# jr-support_v4.net
KiCad netlist of a schematic drawn in EAGLE
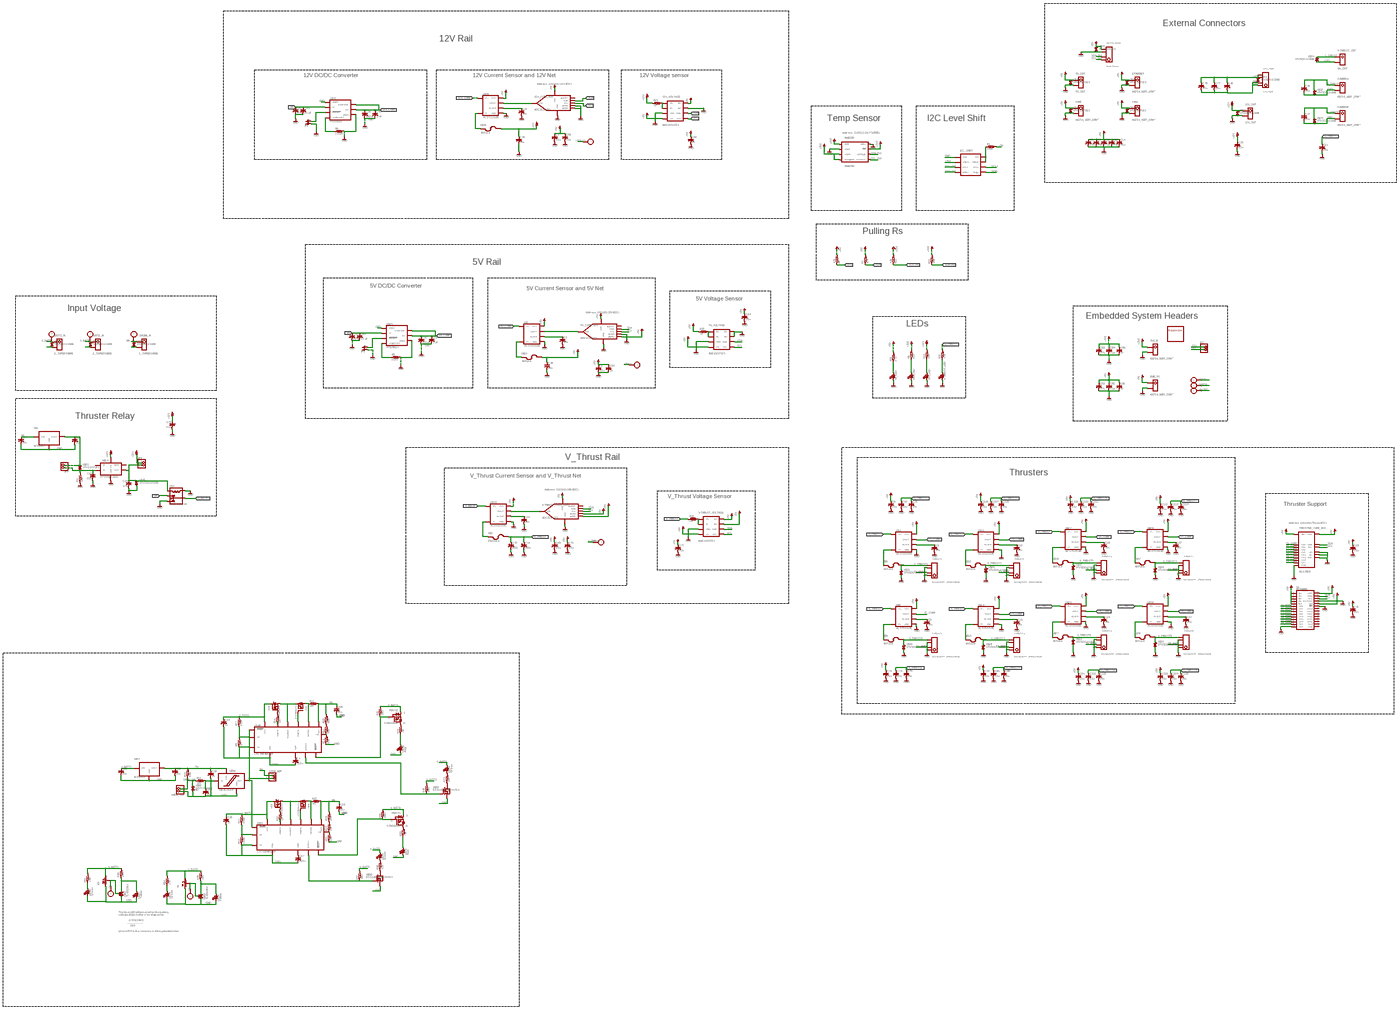
[diagram p0: schematic, sheet 1, overview]
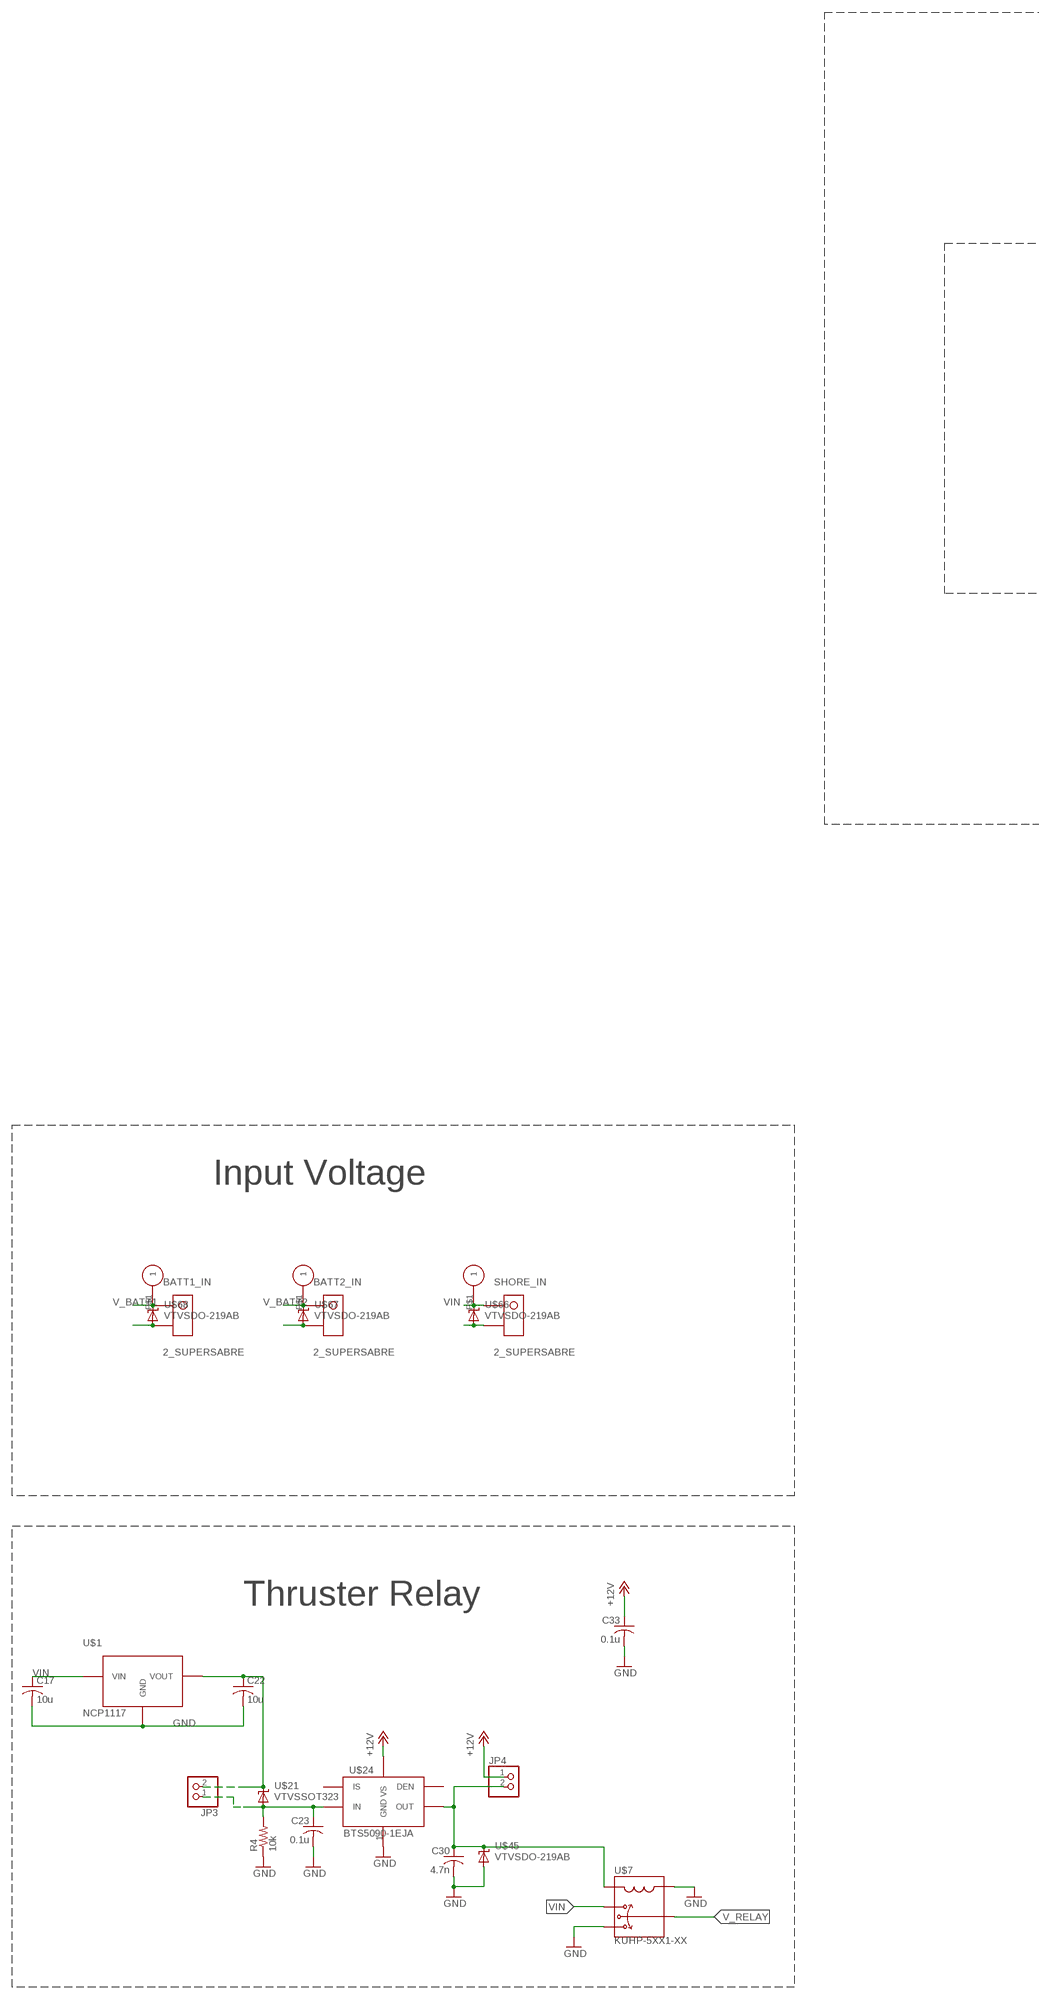
[diagram p1: schematic, sheet 1, part 1 of 8]
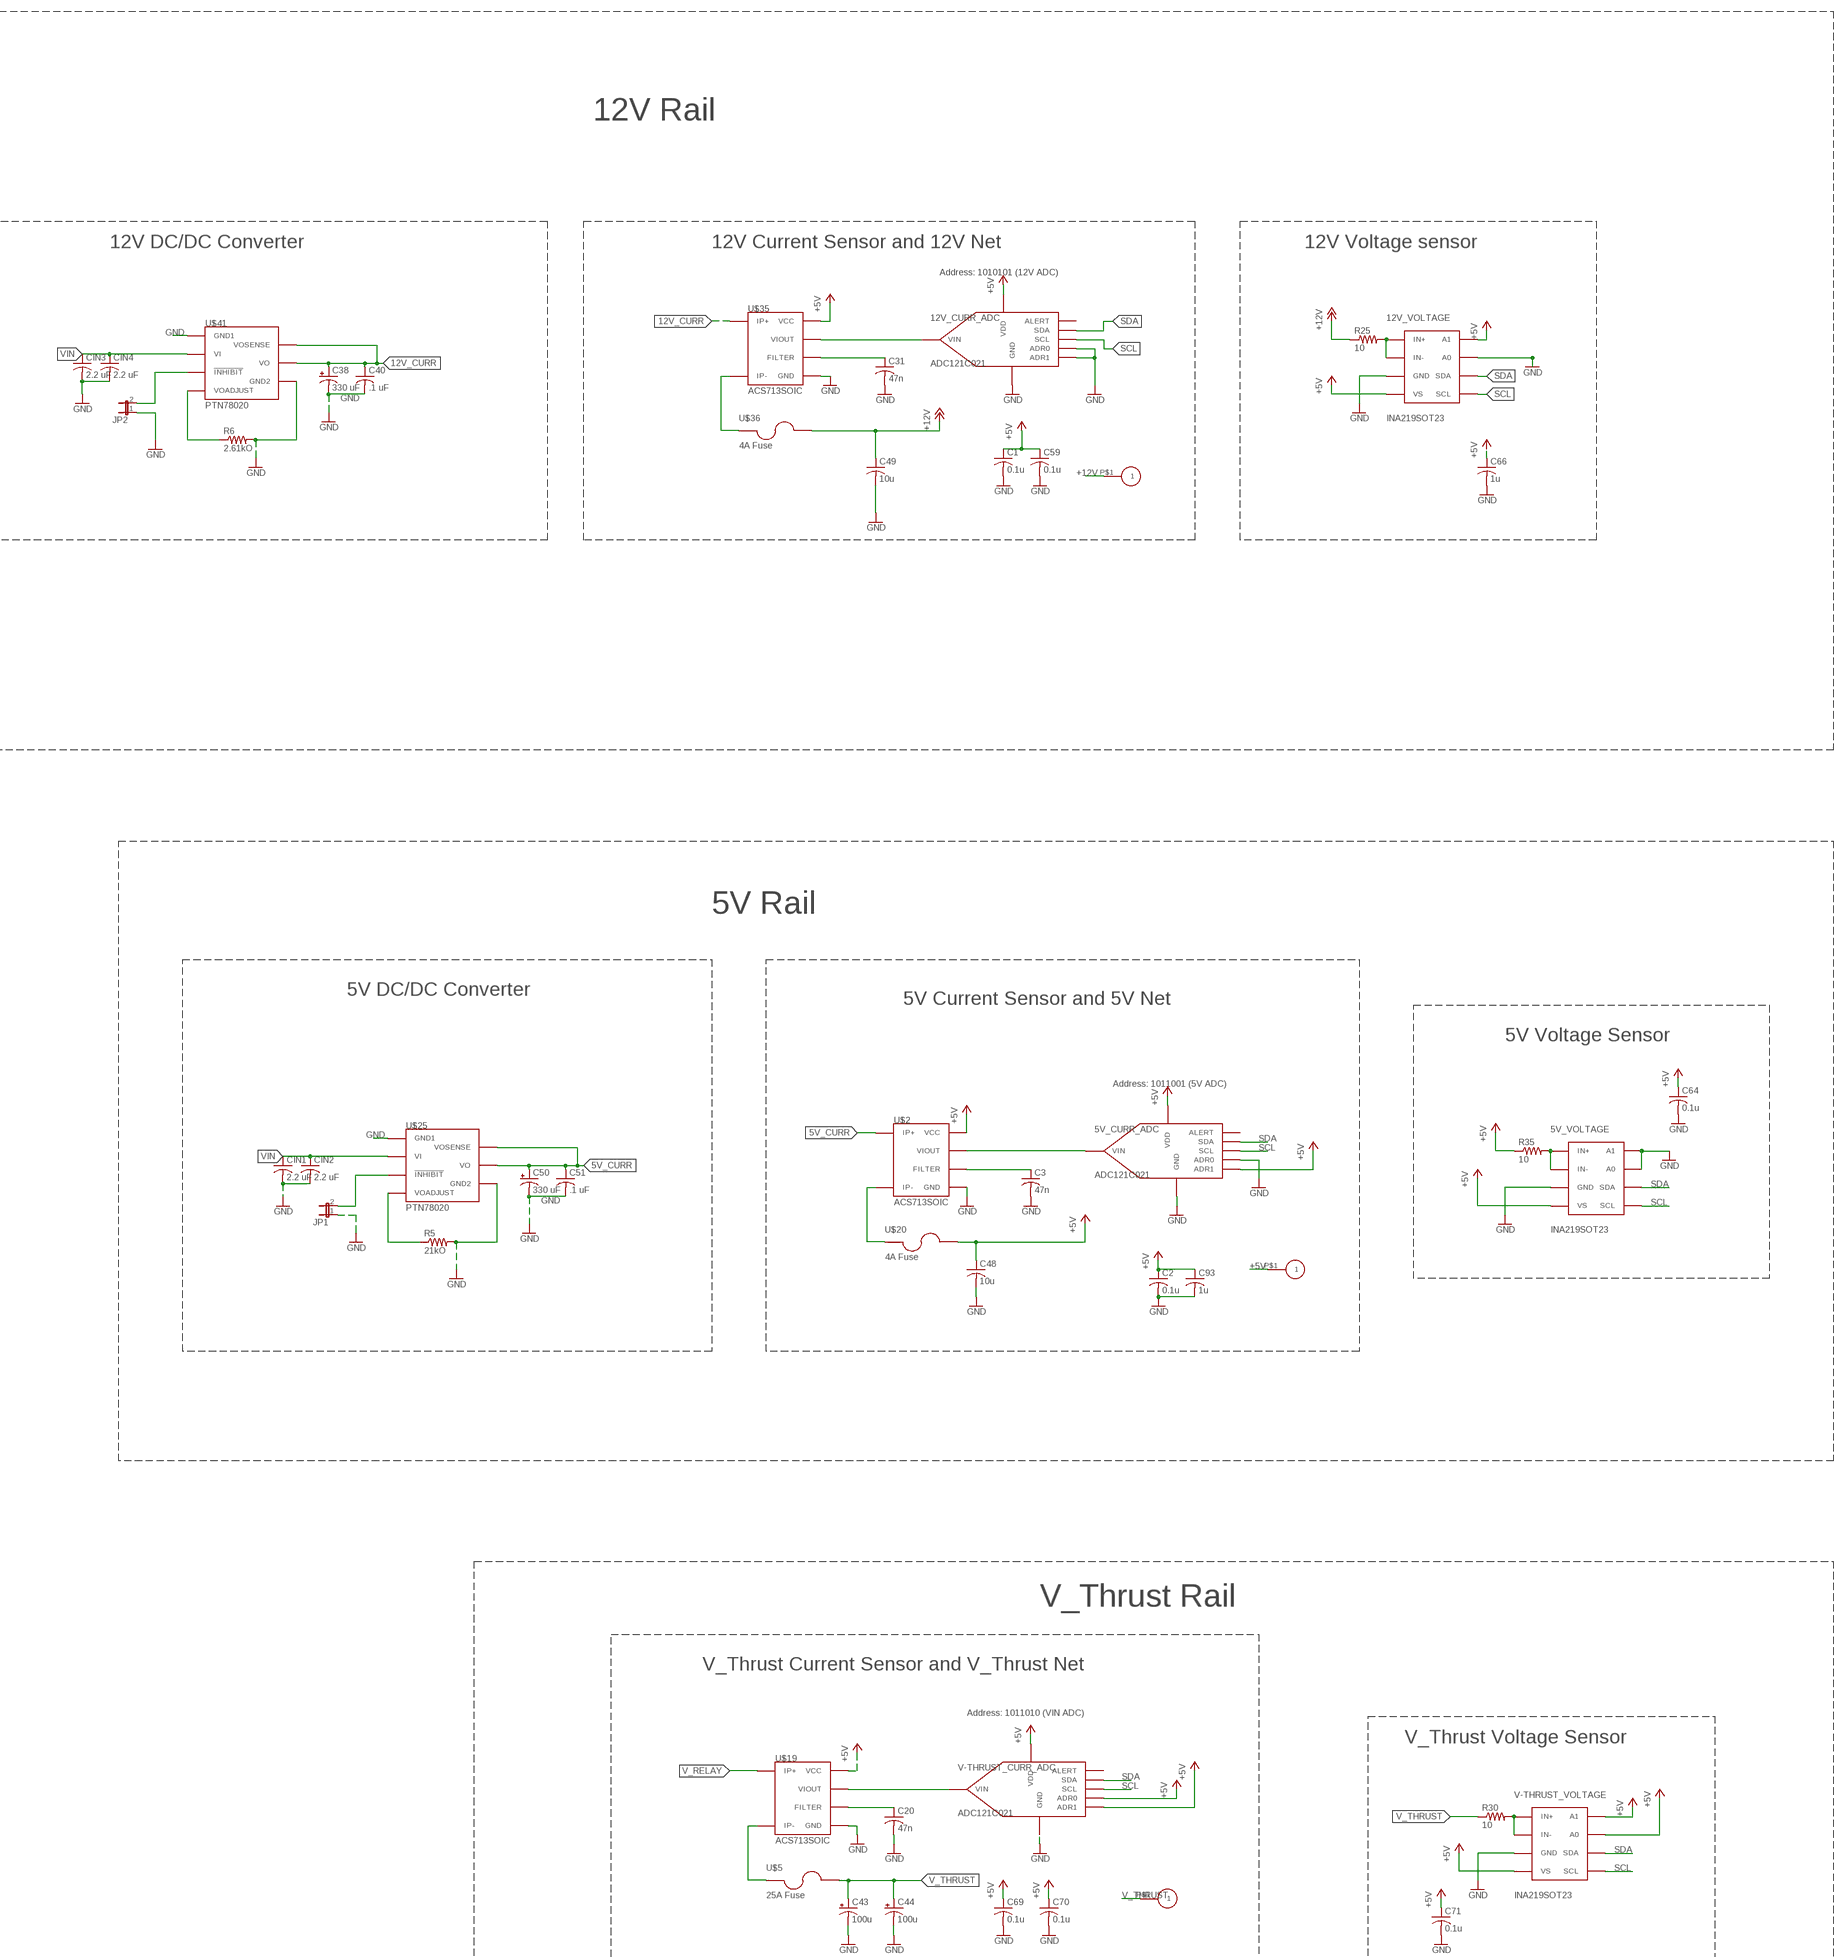
[diagram p2: schematic, sheet 1, part 2 of 8]
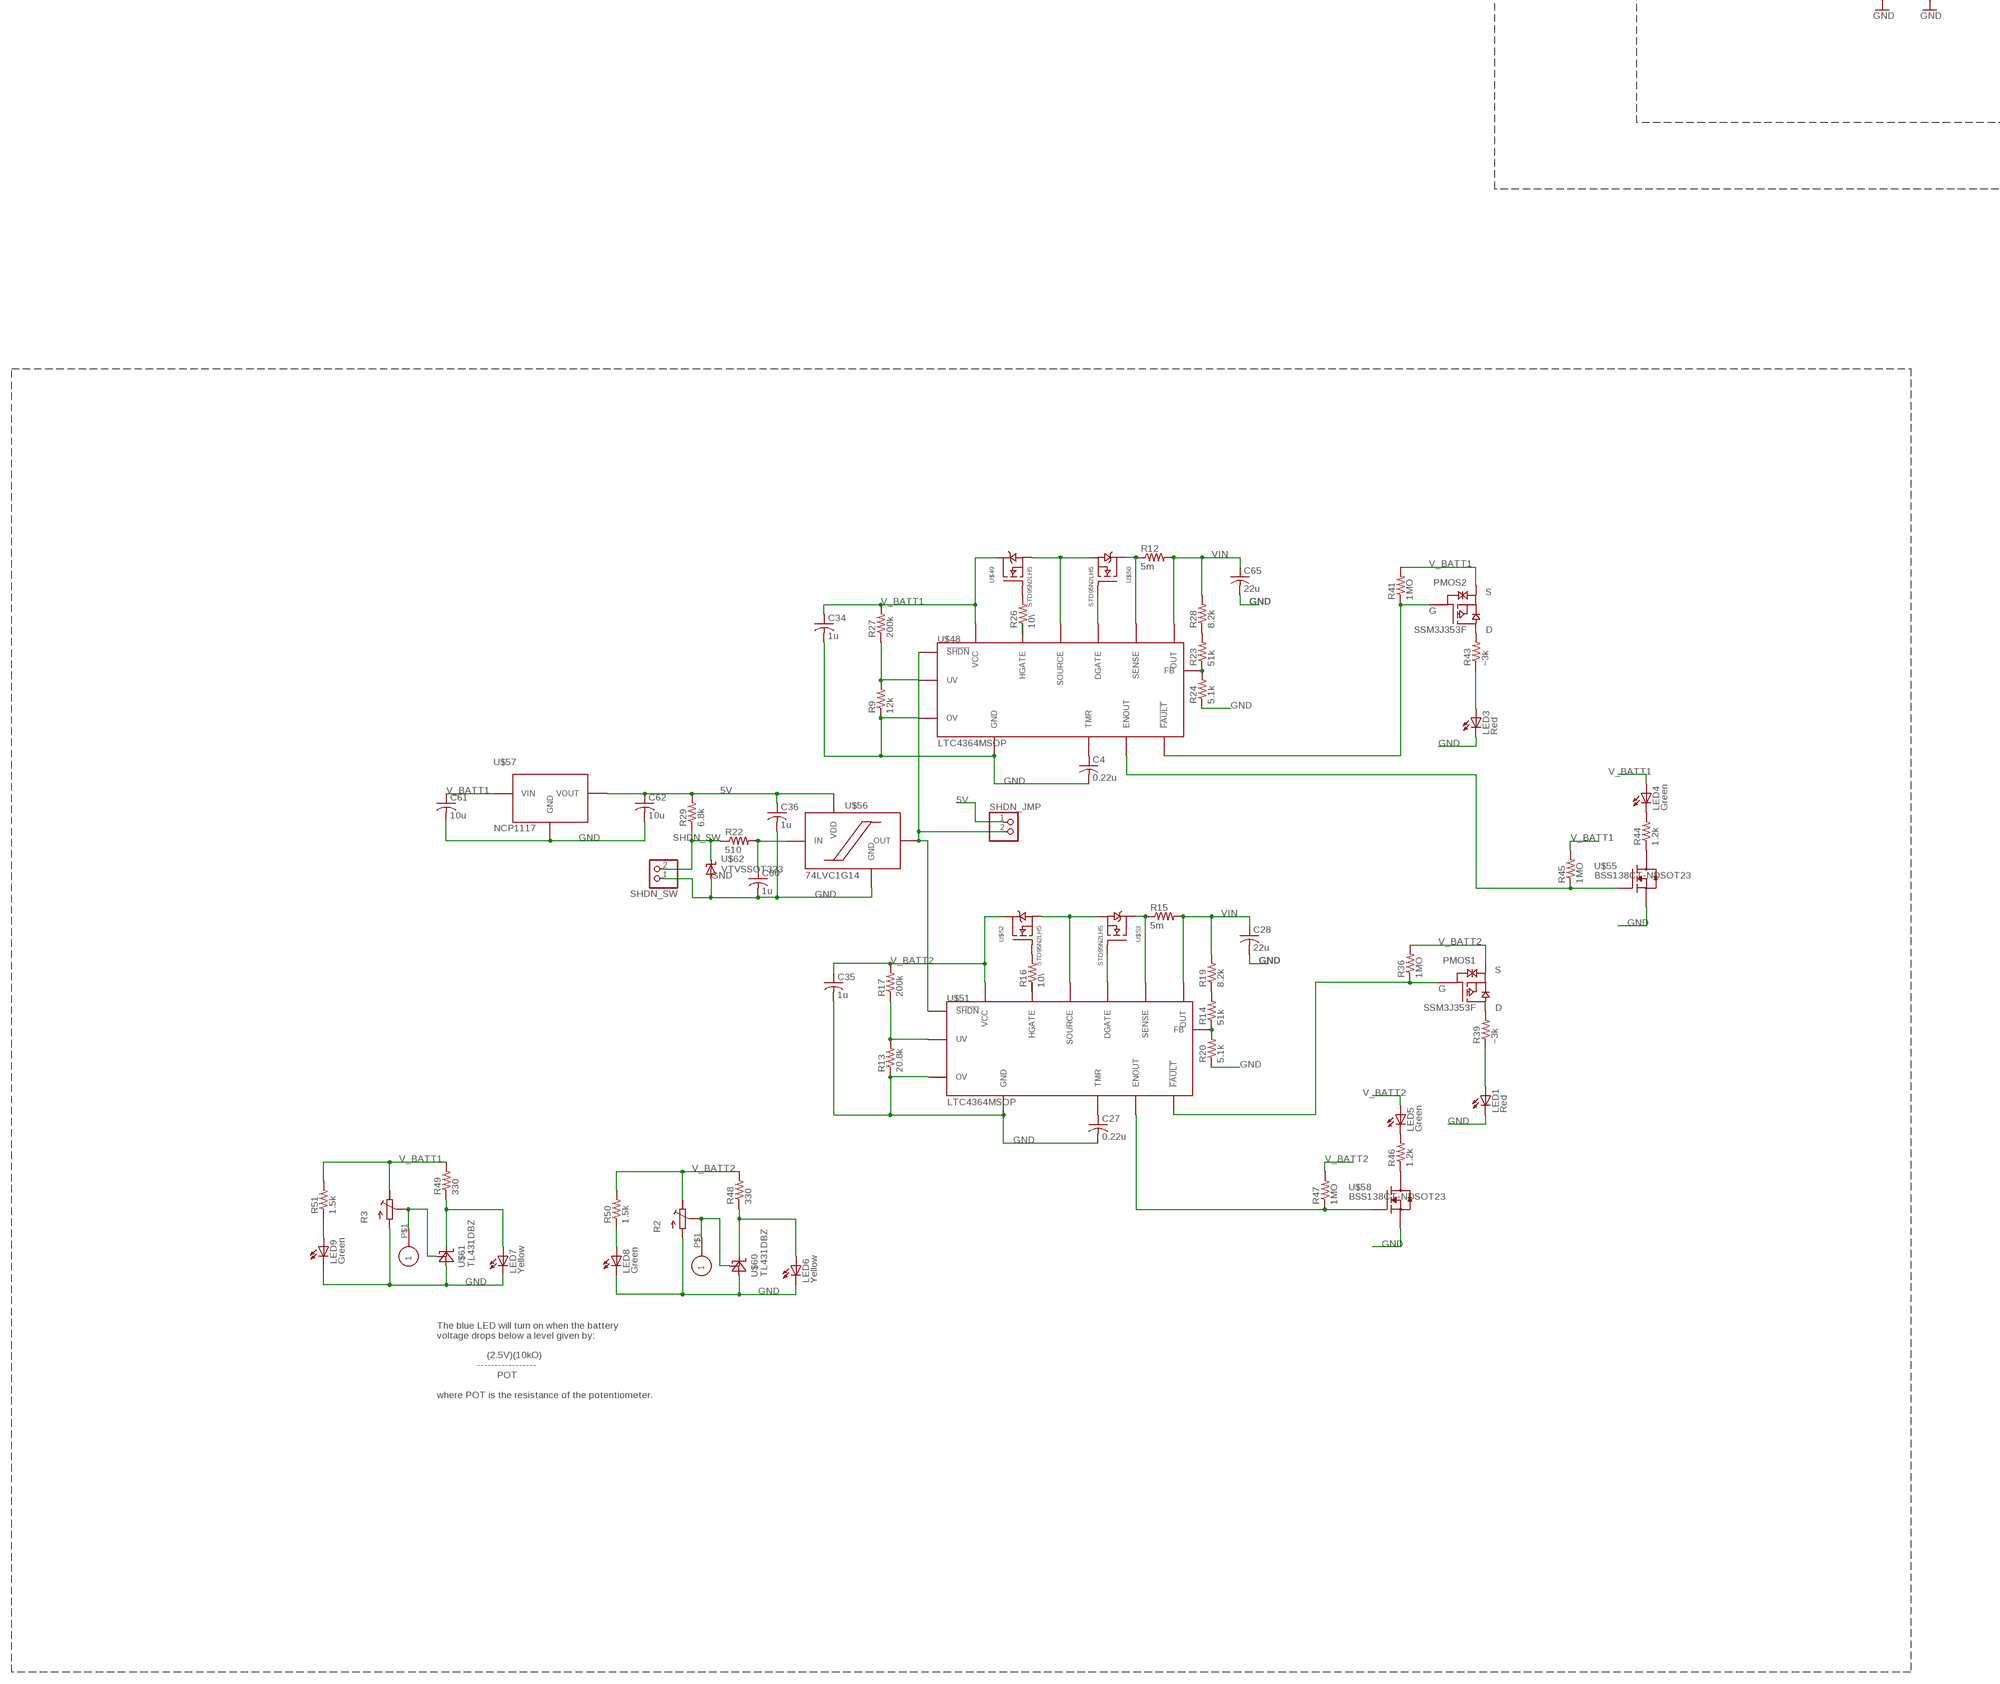
[diagram p3: schematic, sheet 1, part 3 of 8]
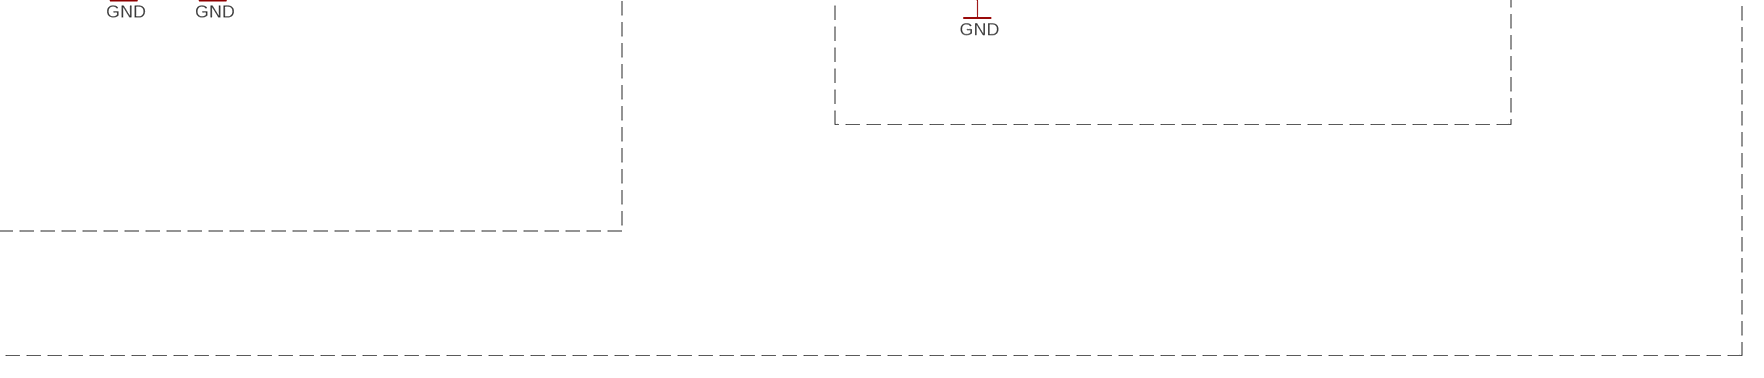
[diagram p4: schematic, sheet 1, part 4 of 8]
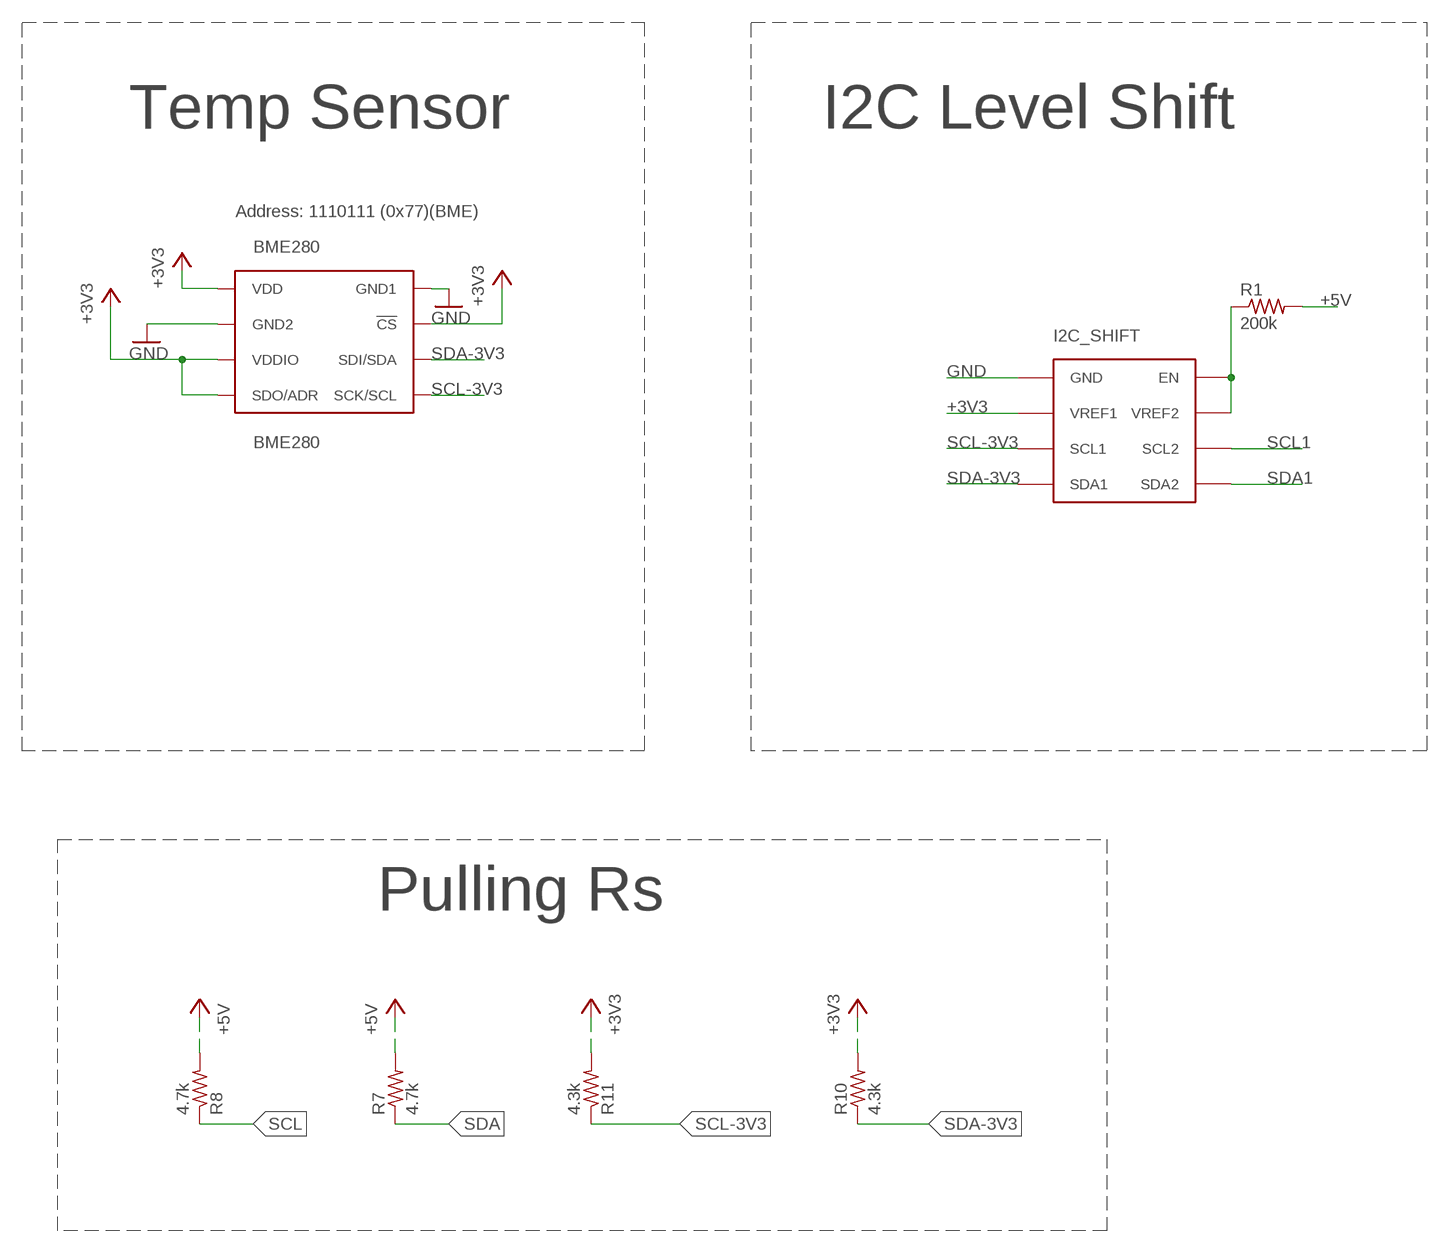
[diagram p5: schematic, sheet 1, part 5 of 8]
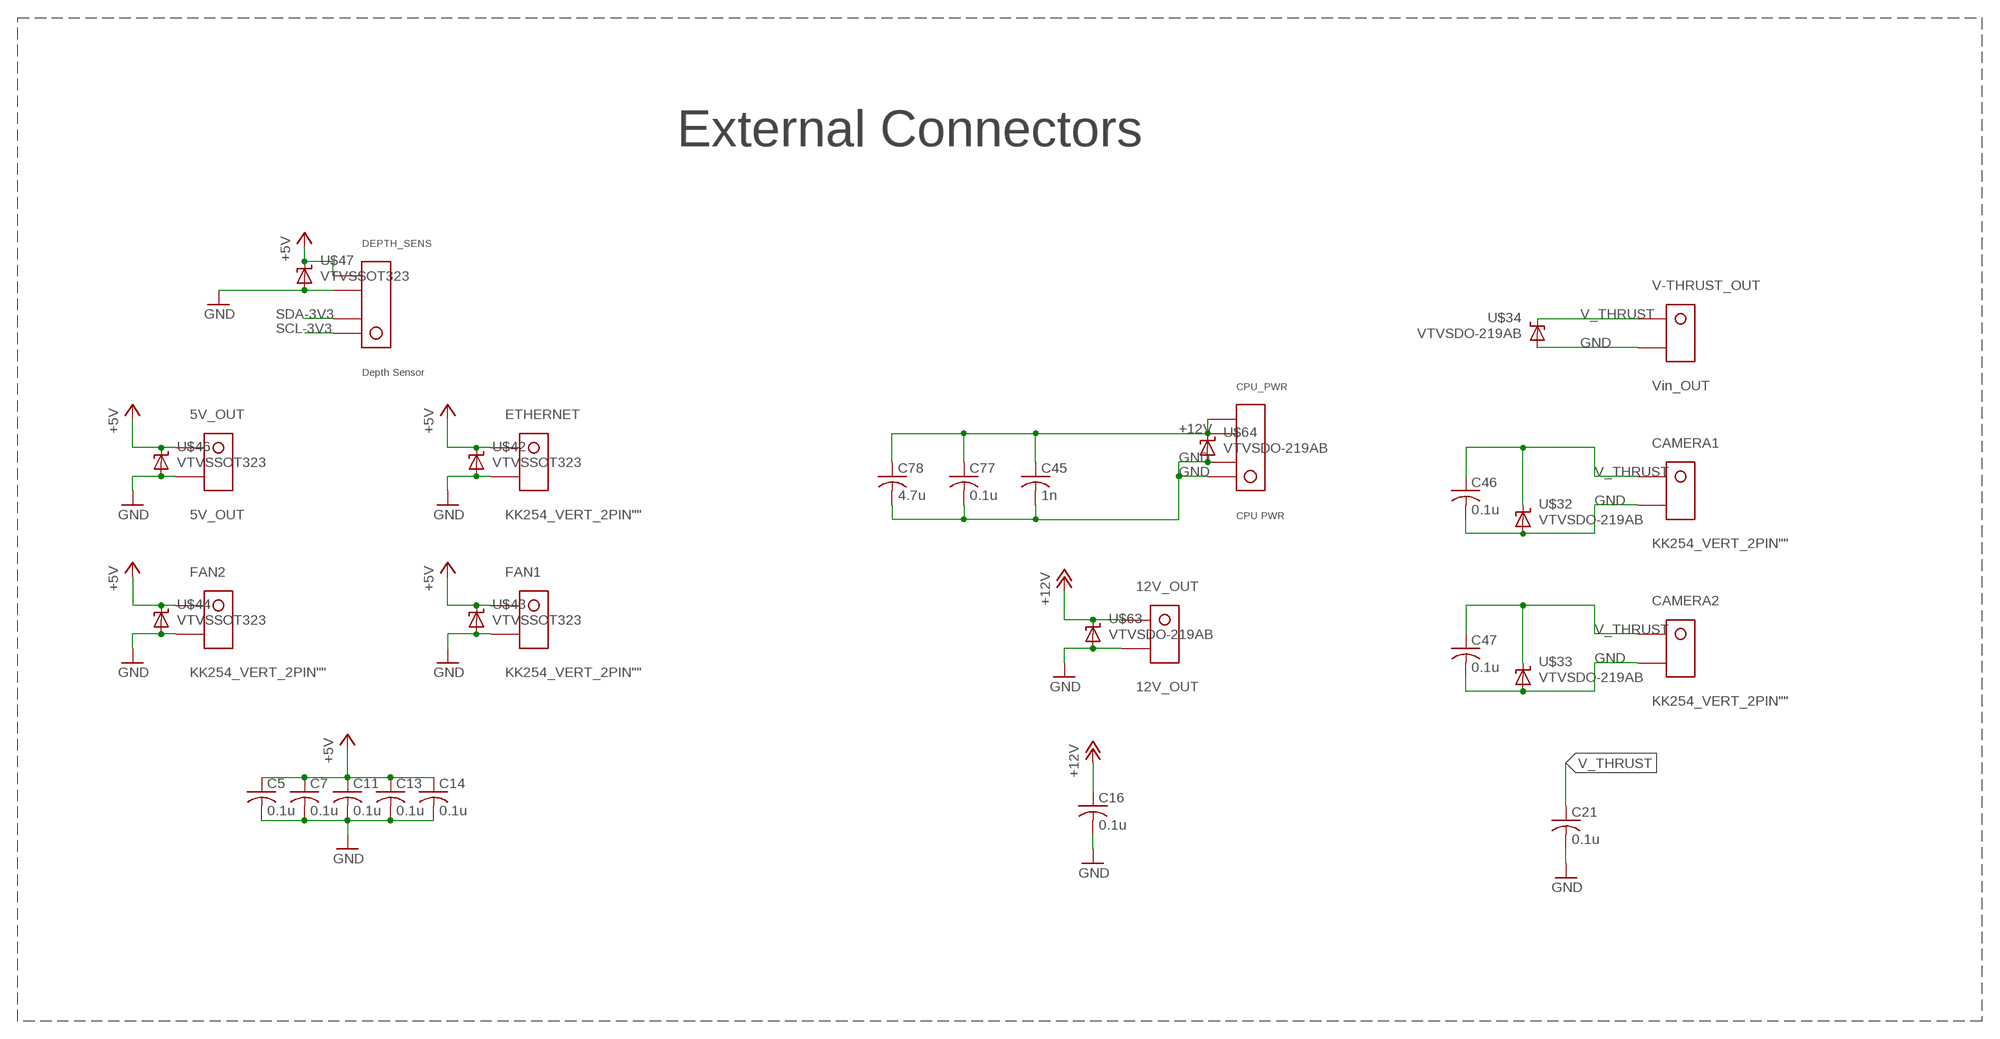
[diagram p6: schematic, sheet 1, part 6 of 8]
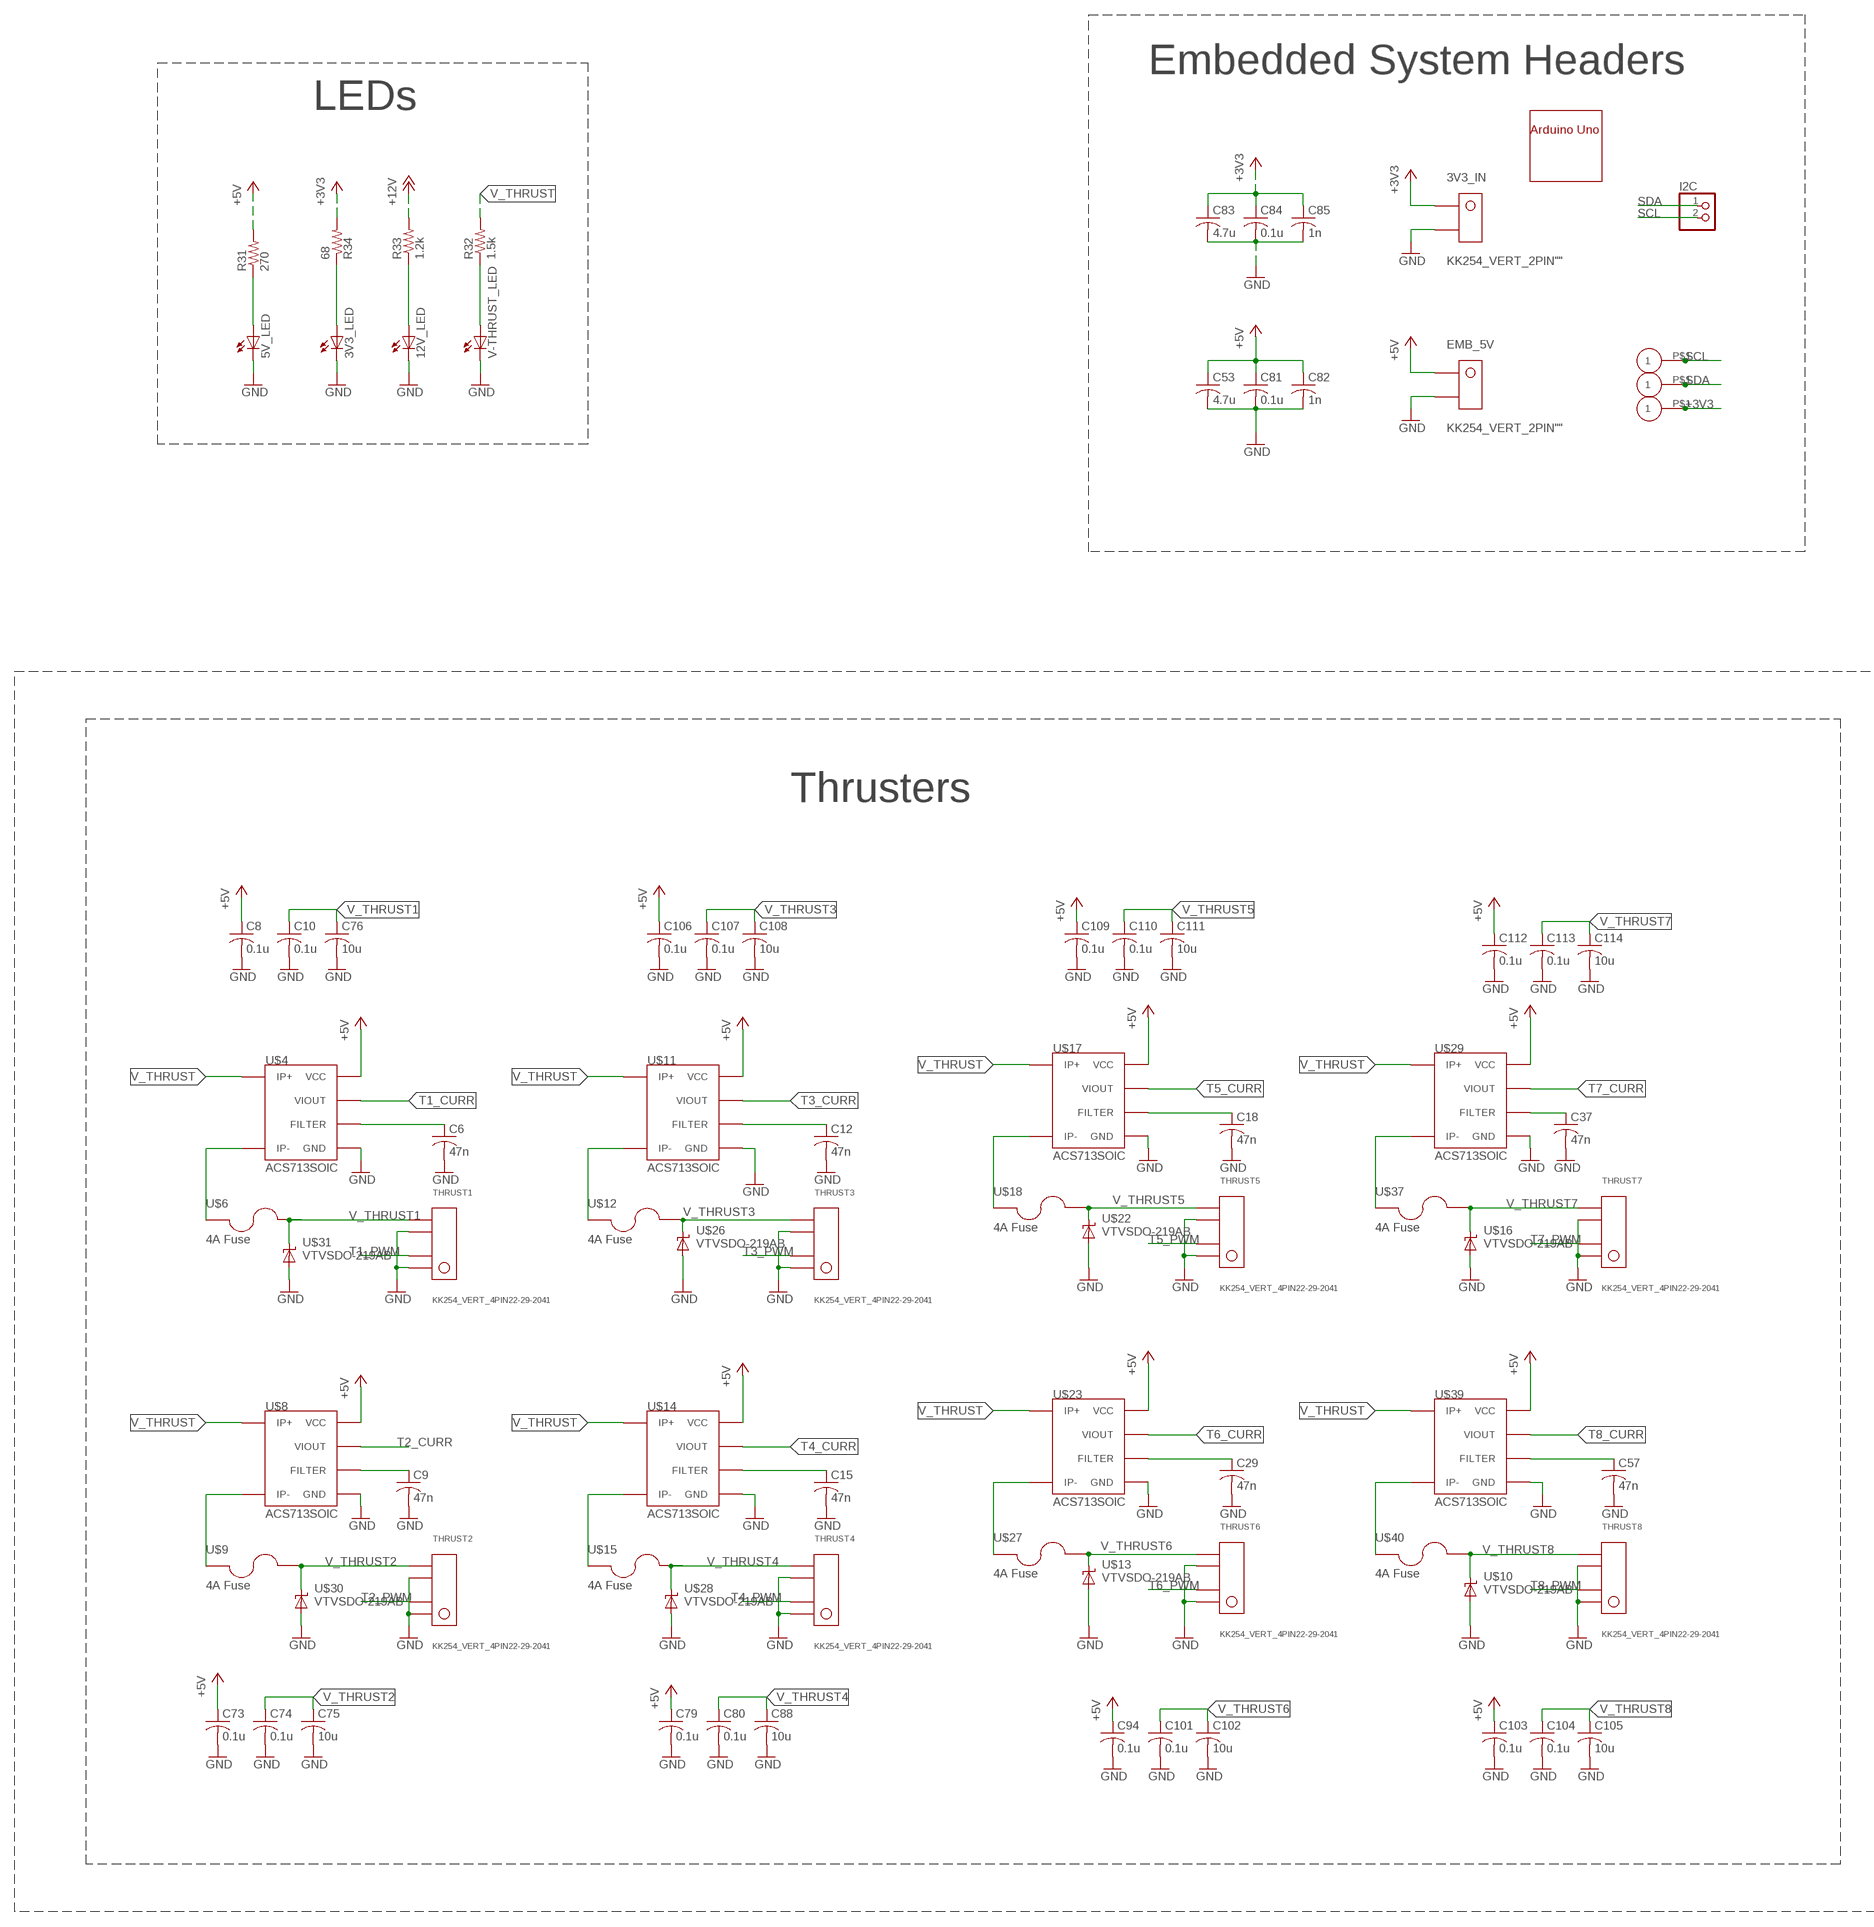
[diagram p7: schematic, sheet 1, part 7 of 8]
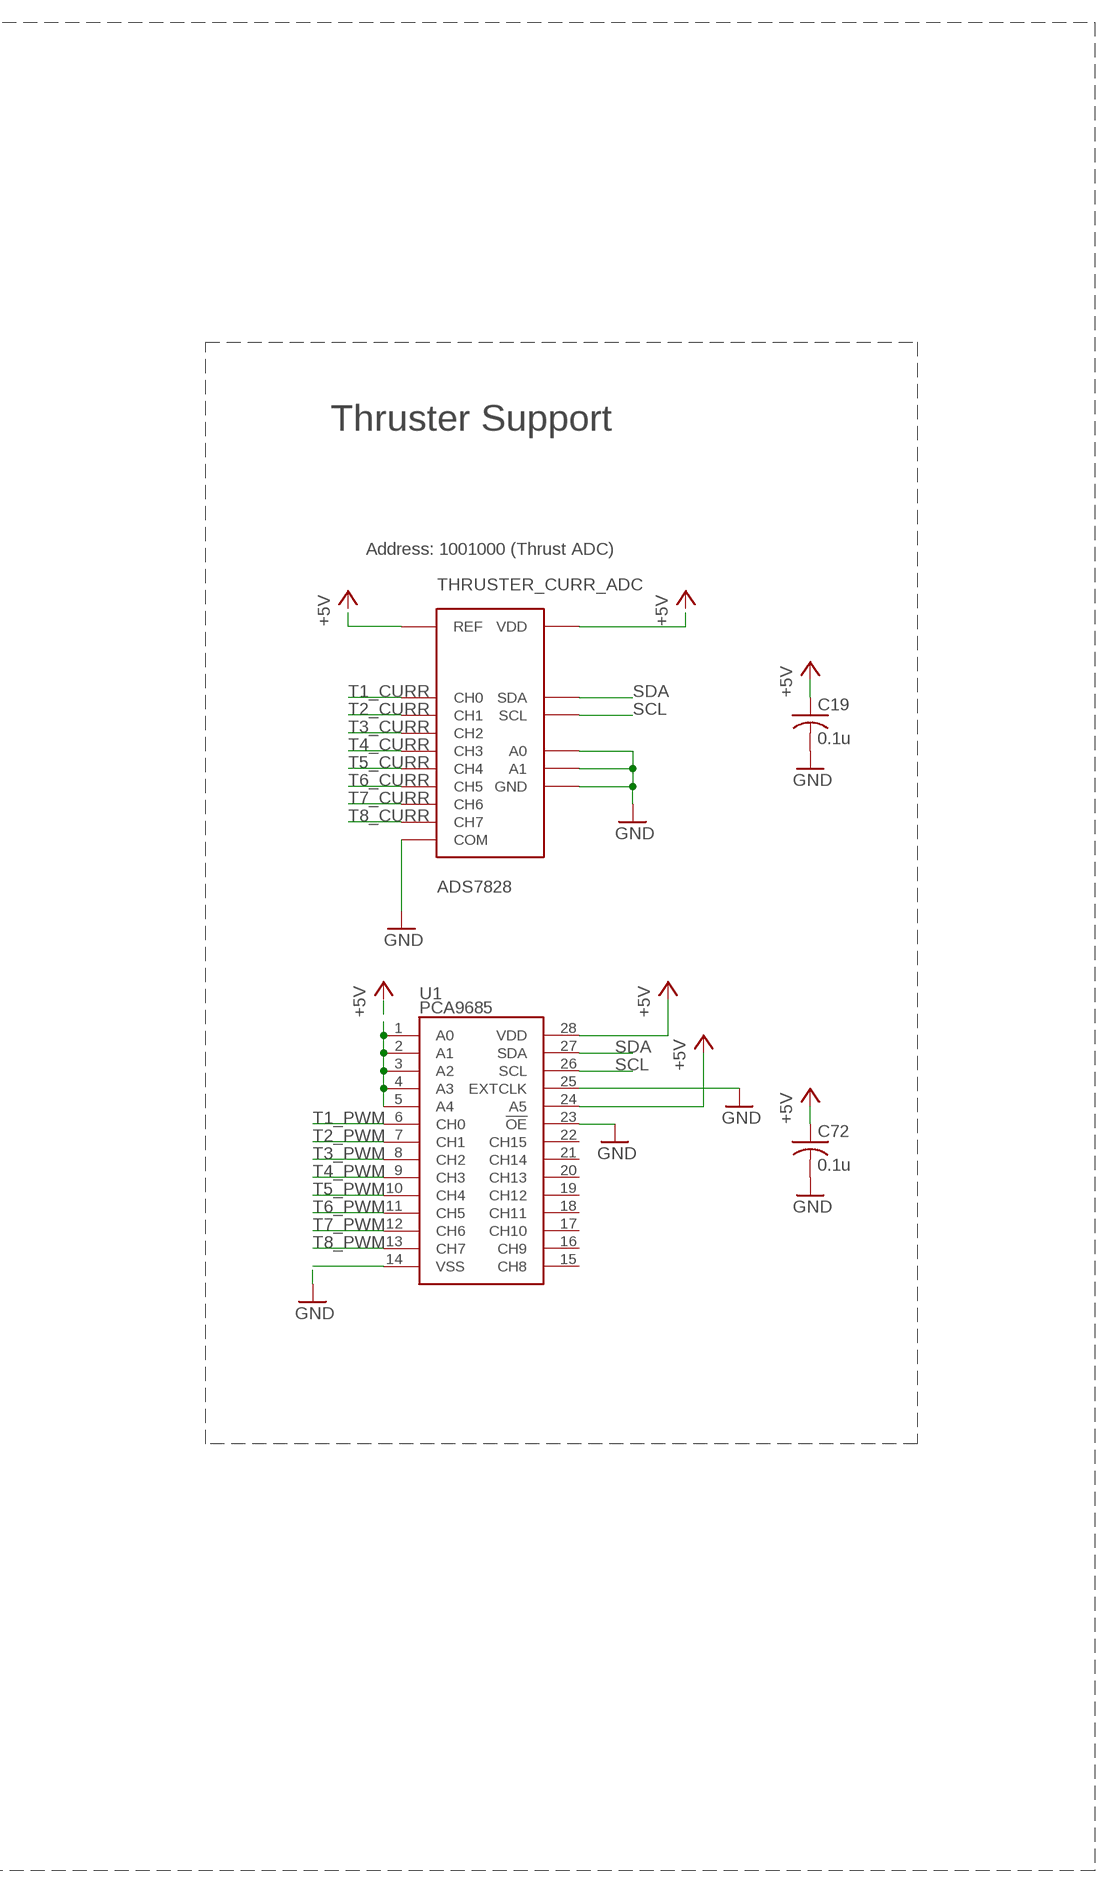
[diagram p8: schematic, sheet 1, part 8 of 8]

(export (version "E")
  (design (tool "Eeschema 10.0.6"))
  (components
    (comp (ref "3V3_IN")
      (value "KK254_VERT_2PIN\"\"")
      (footprint "eagle-import:KK254_VERT_2PIN")
      (libsource (lib "eagle-import") (part "KK254_VERT_2PIN{dblquote}{dblquote}"))
    )
    (comp (ref "3V3_LED")
      (value "0805_LED")
      (footprint "eagle-import:0805")
      (libsource (lib "eagle-import") (part "0805_LED"))
    )
    (comp (ref "5V_CURR_ADC")
      (value "ADC121C021")
      (footprint "eagle-import:VSSOP-8")
      (libsource (lib "eagle-import") (part "ADC121C021"))
    )
    (comp (ref "5V_LED")
      (value "0805_LED")
      (footprint "eagle-import:0805")
      (libsource (lib "eagle-import") (part "0805_LED"))
    )
    (comp (ref "5V_OUT")
      (value "5V_OUT")
      (footprint "eagle-import:KK254_VERT_2PIN")
      (libsource (lib "eagle-import") (part "KK254_VERT_2PIN{dblquote}{dblquote}"))
    )
    (comp (ref "5V_VOLTAGE")
      (value "INA219SOT23")
      (footprint "eagle-import:SOT-23-8")
      (libsource (lib "eagle-import") (part "INA219SOT23"))
    )
    (comp (ref "12V_CURR_ADC")
      (value "ADC121C021")
      (footprint "eagle-import:VSSOP-8")
      (libsource (lib "eagle-import") (part "ADC121C021"))
    )
    (comp (ref "12V_LED")
      (value "0805_LED")
      (footprint "eagle-import:0805")
      (libsource (lib "eagle-import") (part "0805_LED"))
    )
    (comp (ref "12V_OUT")
      (value "12V_OUT")
      (footprint "eagle-import:KK254_VERT_2PIN")
      (libsource (lib "eagle-import") (part "KK254_VERT_2PIN{dblquote}{dblquote}"))
    )
    (comp (ref "12V_VOLTAGE")
      (value "INA219SOT23")
      (footprint "eagle-import:SOT-23-8")
      (libsource (lib "eagle-import") (part "INA219SOT23"))
    )
    (comp (ref "BATT1_IN")
      (value "2_SUPERSABRE")
      (footprint "eagle-import:SUPERSABRE_2CIRCUIT")
      (libsource (lib "eagle-import") (part "2_SUPERSABRE"))
    )
    (comp (ref "BATT2_IN")
      (value "2_SUPERSABRE")
      (footprint "eagle-import:SUPERSABRE_2CIRCUIT")
      (libsource (lib "eagle-import") (part "2_SUPERSABRE"))
    )
    (comp (ref "BME280")
      (value "BME280")
      (footprint "eagle-import:BME280_LGA")
      (libsource (lib "eagle-import") (part "BME280"))
    )
    (comp (ref "C1")
      (value "0.1u")
      (footprint "eagle-import:C0805")
      (libsource (lib "eagle-import") (part "C-USC0805"))
    )
    (comp (ref "C2")
      (value "0.1u")
      (footprint "eagle-import:C0805")
      (libsource (lib "eagle-import") (part "C-USC0805"))
    )
    (comp (ref "C3")
      (value "47n")
      (footprint "eagle-import:C0805")
      (libsource (lib "eagle-import") (part "C-USC0805"))
    )
    (comp (ref "C4")
      (value "0.22u")
      (footprint "eagle-import:C0805")
      (libsource (lib "eagle-import") (part "C-USC0805"))
    )
    (comp (ref "C5")
      (value "0.1u")
      (footprint "eagle-import:C0805")
      (libsource (lib "eagle-import") (part "C-USC0805"))
    )
    (comp (ref "C6")
      (value "47n")
      (footprint "eagle-import:C0805")
      (libsource (lib "eagle-import") (part "C-USC0805"))
    )
    (comp (ref "C7")
      (value "0.1u")
      (footprint "eagle-import:C0805")
      (libsource (lib "eagle-import") (part "C-USC0805"))
    )
    (comp (ref "C8")
      (value "0.1u")
      (footprint "eagle-import:C0805")
      (libsource (lib "eagle-import") (part "C-USC0805"))
    )
    (comp (ref "C9")
      (value "47n")
      (footprint "eagle-import:C0805")
      (libsource (lib "eagle-import") (part "C-USC0805"))
    )
    (comp (ref "C10")
      (value "0.1u")
      (footprint "eagle-import:C0805")
      (libsource (lib "eagle-import") (part "C-USC0805"))
    )
    (comp (ref "C11")
      (value "0.1u")
      (footprint "eagle-import:C0805")
      (libsource (lib "eagle-import") (part "C-USC0805"))
    )
    (comp (ref "C12")
      (value "47n")
      (footprint "eagle-import:C0805")
      (libsource (lib "eagle-import") (part "C-USC0805"))
    )
    (comp (ref "C13")
      (value "0.1u")
      (footprint "eagle-import:C0805")
      (libsource (lib "eagle-import") (part "C-USC0805"))
    )
    (comp (ref "C14")
      (value "0.1u")
      (footprint "eagle-import:C0805")
      (libsource (lib "eagle-import") (part "C-USC0805"))
    )
    (comp (ref "C15")
      (value "47n")
      (footprint "eagle-import:C0805")
      (libsource (lib "eagle-import") (part "C-USC0805"))
    )
    (comp (ref "C16")
      (value "0.1u")
      (footprint "eagle-import:C0805")
      (libsource (lib "eagle-import") (part "C-USC0805"))
    )
    (comp (ref "C17")
      (value "10u")
      (footprint "eagle-import:C0805")
      (libsource (lib "eagle-import") (part "C-USC0805"))
    )
    (comp (ref "C18")
      (value "47n")
      (footprint "eagle-import:C0805")
      (libsource (lib "eagle-import") (part "C-USC0805"))
    )
    (comp (ref "C19")
      (value "0.1u")
      (footprint "eagle-import:C0805")
      (libsource (lib "eagle-import") (part "C-USC0805"))
    )
    (comp (ref "C20")
      (value "47n")
      (footprint "eagle-import:C0805")
      (libsource (lib "eagle-import") (part "C-USC0805"))
    )
    (comp (ref "C21")
      (value "0.1u")
      (footprint "eagle-import:C0805")
      (libsource (lib "eagle-import") (part "C-USC0805"))
    )
    (comp (ref "C22")
      (value "10u")
      (footprint "eagle-import:C0805")
      (libsource (lib "eagle-import") (part "C-USC0805"))
    )
    (comp (ref "C23")
      (value "0.1u")
      (footprint "eagle-import:C0805")
      (libsource (lib "eagle-import") (part "C-USC0805"))
    )
    (comp (ref "C27")
      (value "0.22u")
      (footprint "eagle-import:C0805")
      (libsource (lib "eagle-import") (part "C-USC0805"))
    )
    (comp (ref "C28")
      (value "22u")
      (footprint "eagle-import:C0805")
      (libsource (lib "eagle-import") (part "C-USC0805"))
    )
    (comp (ref "C29")
      (value "47n")
      (footprint "eagle-import:C0805")
      (libsource (lib "eagle-import") (part "C-USC0805"))
    )
    (comp (ref "C30")
      (value "4.7n")
      (footprint "eagle-import:C0805")
      (libsource (lib "eagle-import") (part "C-USC0805"))
    )
    (comp (ref "C31")
      (value "47n")
      (footprint "eagle-import:C0805")
      (libsource (lib "eagle-import") (part "C-USC0805"))
    )
    (comp (ref "C33")
      (value "0.1u")
      (footprint "eagle-import:C0805")
      (libsource (lib "eagle-import") (part "C-USC0805"))
    )
    (comp (ref "C34")
      (value "1u")
      (footprint "eagle-import:C0805")
      (libsource (lib "eagle-import") (part "C-USC0805"))
    )
    (comp (ref "C35")
      (value "1u")
      (footprint "eagle-import:C0805")
      (libsource (lib "eagle-import") (part "C-USC0805"))
    )
    (comp (ref "C36")
      (value "1u")
      (footprint "eagle-import:C0805")
      (libsource (lib "eagle-import") (part "C-USC0805"))
    )
    (comp (ref "C37")
      (value "47n")
      (footprint "eagle-import:C0805")
      (libsource (lib "eagle-import") (part "C-USC0805"))
    )
    (comp (ref "C38")
      (value "330 uF")
      (footprint "eagle-import:CKR_D10")
      (libsource (lib "eagle-import") (part "CPOL-USCKR_D10"))
    )
    (comp (ref "C40")
      (value ".1 uF")
      (footprint "eagle-import:C0805")
      (libsource (lib "eagle-import") (part "C-USC0805"))
    )
    (comp (ref "C43")
      (value "100u")
      (footprint "eagle-import:140CLH-0810")
      (libsource (lib "eagle-import") (part "CPOL-US140CLH-0810"))
    )
    (comp (ref "C44")
      (value "100u")
      (footprint "eagle-import:140CLH-0810")
      (libsource (lib "eagle-import") (part "CPOL-US140CLH-0810"))
    )
    (comp (ref "C45")
      (value "1n")
      (footprint "eagle-import:C0805")
      (libsource (lib "eagle-import") (part "C-USC0805"))
    )
    (comp (ref "C46")
      (value "0.1u")
      (footprint "eagle-import:C0805")
      (libsource (lib "eagle-import") (part "C-USC0805"))
    )
    (comp (ref "C47")
      (value "0.1u")
      (footprint "eagle-import:C0805")
      (libsource (lib "eagle-import") (part "C-USC0805"))
    )
    (comp (ref "C48")
      (value "10u")
      (footprint "eagle-import:C0805")
      (libsource (lib "eagle-import") (part "C-USC0805"))
    )
    (comp (ref "C49")
      (value "10u")
      (footprint "eagle-import:C0805")
      (libsource (lib "eagle-import") (part "C-USC0805"))
    )
    (comp (ref "C50")
      (value "330 uF")
      (footprint "eagle-import:CKR_D10")
      (libsource (lib "eagle-import") (part "CPOL-USCKR_D10"))
    )
    (comp (ref "C51")
      (value ".1 uF")
      (footprint "eagle-import:C0805")
      (libsource (lib "eagle-import") (part "C-USC0805"))
    )
    (comp (ref "C53")
      (value "4.7u")
      (footprint "eagle-import:C0805")
      (libsource (lib "eagle-import") (part "C-USC0805"))
    )
    (comp (ref "C57")
      (value "47n")
      (footprint "eagle-import:C0805")
      (libsource (lib "eagle-import") (part "C-USC0805"))
    )
    (comp (ref "C59")
      (value "0.1u")
      (footprint "eagle-import:C0805")
      (libsource (lib "eagle-import") (part "C-USC0805"))
    )
    (comp (ref "C60")
      (value "1u")
      (footprint "eagle-import:C0805")
      (libsource (lib "eagle-import") (part "C-USC0805"))
    )
    (comp (ref "C61")
      (value "10u")
      (footprint "eagle-import:C0805")
      (libsource (lib "eagle-import") (part "C-USC0805"))
    )
    (comp (ref "C62")
      (value "10u")
      (footprint "eagle-import:C0805")
      (libsource (lib "eagle-import") (part "C-USC0805"))
    )
    (comp (ref "C64")
      (value "0.1u")
      (footprint "eagle-import:C0805")
      (libsource (lib "eagle-import") (part "C-USC0805"))
    )
    (comp (ref "C65")
      (value "22u")
      (footprint "eagle-import:C0805")
      (libsource (lib "eagle-import") (part "C-USC0805"))
    )
    (comp (ref "C66")
      (value "1u")
      (footprint "eagle-import:C0805")
      (libsource (lib "eagle-import") (part "C-USC0805"))
    )
    (comp (ref "C69")
      (value "0.1u")
      (footprint "eagle-import:C0805")
      (libsource (lib "eagle-import") (part "C-USC0805"))
    )
    (comp (ref "C70")
      (value "0.1u")
      (footprint "eagle-import:C0805")
      (libsource (lib "eagle-import") (part "C-USC0805"))
    )
    (comp (ref "C71")
      (value "0.1u")
      (footprint "eagle-import:C0805")
      (libsource (lib "eagle-import") (part "C-USC0805"))
    )
    (comp (ref "C72")
      (value "0.1u")
      (footprint "eagle-import:C0805")
      (libsource (lib "eagle-import") (part "C-USC0805"))
    )
    (comp (ref "C73")
      (value "0.1u")
      (footprint "eagle-import:C0805")
      (libsource (lib "eagle-import") (part "C-USC0805"))
    )
    (comp (ref "C74")
      (value "0.1u")
      (footprint "eagle-import:C0805")
      (libsource (lib "eagle-import") (part "C-USC0805"))
    )
    (comp (ref "C75")
      (value "10u")
      (footprint "eagle-import:C0805")
      (libsource (lib "eagle-import") (part "C-USC0805"))
    )
    (comp (ref "C76")
      (value "10u")
      (footprint "eagle-import:C0805")
      (libsource (lib "eagle-import") (part "C-USC0805"))
    )
    (comp (ref "C77")
      (value "0.1u")
      (footprint "eagle-import:C0805")
      (libsource (lib "eagle-import") (part "C-USC0805"))
    )
    (comp (ref "C78")
      (value "4.7u")
      (footprint "eagle-import:C0805")
      (libsource (lib "eagle-import") (part "C-USC0805"))
    )
    (comp (ref "C79")
      (value "0.1u")
      (footprint "eagle-import:C0805")
      (libsource (lib "eagle-import") (part "C-USC0805"))
    )
    (comp (ref "C80")
      (value "0.1u")
      (footprint "eagle-import:C0805")
      (libsource (lib "eagle-import") (part "C-USC0805"))
    )
    (comp (ref "C81")
      (value "0.1u")
      (footprint "eagle-import:C0805")
      (libsource (lib "eagle-import") (part "C-USC0805"))
    )
    (comp (ref "C82")
      (value "1n")
      (footprint "eagle-import:C0805")
      (libsource (lib "eagle-import") (part "C-USC0805"))
    )
    (comp (ref "C83")
      (value "4.7u")
      (footprint "eagle-import:C0805")
      (libsource (lib "eagle-import") (part "C-USC0805"))
    )
    (comp (ref "C84")
      (value "0.1u")
      (footprint "eagle-import:C0805")
      (libsource (lib "eagle-import") (part "C-USC0805"))
    )
    (comp (ref "C85")
      (value "1n")
      (footprint "eagle-import:C0805")
      (libsource (lib "eagle-import") (part "C-USC0805"))
    )
    (comp (ref "C88")
      (value "10u")
      (footprint "eagle-import:C0805")
      (libsource (lib "eagle-import") (part "C-USC0805"))
    )
    (comp (ref "C93")
      (value "1u")
      (footprint "eagle-import:C0805")
      (libsource (lib "eagle-import") (part "C-USC0805"))
    )
    (comp (ref "C94")
      (value "0.1u")
      (footprint "eagle-import:C0805")
      (libsource (lib "eagle-import") (part "C-USC0805"))
    )
    (comp (ref "C101")
      (value "0.1u")
      (footprint "eagle-import:C0805")
      (libsource (lib "eagle-import") (part "C-USC0805"))
    )
    (comp (ref "C102")
      (value "10u")
      (footprint "eagle-import:C0805")
      (libsource (lib "eagle-import") (part "C-USC0805"))
    )
    (comp (ref "C103")
      (value "0.1u")
      (footprint "eagle-import:C0805")
      (libsource (lib "eagle-import") (part "C-USC0805"))
    )
    (comp (ref "C104")
      (value "0.1u")
      (footprint "eagle-import:C0805")
      (libsource (lib "eagle-import") (part "C-USC0805"))
    )
    (comp (ref "C105")
      (value "10u")
      (footprint "eagle-import:C0805")
      (libsource (lib "eagle-import") (part "C-USC0805"))
    )
    (comp (ref "C106")
      (value "0.1u")
      (footprint "eagle-import:C0805")
      (libsource (lib "eagle-import") (part "C-USC0805"))
    )
    (comp (ref "C107")
      (value "0.1u")
      (footprint "eagle-import:C0805")
      (libsource (lib "eagle-import") (part "C-USC0805"))
    )
    (comp (ref "C108")
      (value "10u")
      (footprint "eagle-import:C0805")
      (libsource (lib "eagle-import") (part "C-USC0805"))
    )
    (comp (ref "C109")
      (value "0.1u")
      (footprint "eagle-import:C0805")
      (libsource (lib "eagle-import") (part "C-USC0805"))
    )
    (comp (ref "C110")
      (value "0.1u")
      (footprint "eagle-import:C0805")
      (libsource (lib "eagle-import") (part "C-USC0805"))
    )
    (comp (ref "C111")
      (value "10u")
      (footprint "eagle-import:C0805")
      (libsource (lib "eagle-import") (part "C-USC0805"))
    )
    (comp (ref "C112")
      (value "0.1u")
      (footprint "eagle-import:C0805")
      (libsource (lib "eagle-import") (part "C-USC0805"))
    )
    (comp (ref "C113")
      (value "0.1u")
      (footprint "eagle-import:C0805")
      (libsource (lib "eagle-import") (part "C-USC0805"))
    )
    (comp (ref "C114")
      (value "10u")
      (footprint "eagle-import:C0805")
      (libsource (lib "eagle-import") (part "C-USC0805"))
    )
    (comp (ref "CAMERA1")
      (value "KK254_VERT_2PIN\"\"")
      (footprint "eagle-import:KK254_VERT_2PIN")
      (libsource (lib "eagle-import") (part "KK254_VERT_2PIN{dblquote}{dblquote}"))
    )
    (comp (ref "CAMERA2")
      (value "KK254_VERT_2PIN\"\"")
      (footprint "eagle-import:KK254_VERT_2PIN")
      (libsource (lib "eagle-import") (part "KK254_VERT_2PIN{dblquote}{dblquote}"))
    )
    (comp (ref "CIN1")
      (value "2.2 uF")
      (footprint "eagle-import:C1210")
      (libsource (lib "eagle-import") (part "C-USC1210"))
    )
    (comp (ref "CIN2")
      (value "2.2 uF")
      (footprint "eagle-import:C1210")
      (libsource (lib "eagle-import") (part "C-USC1210"))
    )
    (comp (ref "CIN3")
      (value "2.2 uF")
      (footprint "eagle-import:C1210")
      (libsource (lib "eagle-import") (part "C-USC1210"))
    )
    (comp (ref "CIN4")
      (value "2.2 uF")
      (footprint "eagle-import:C1210")
      (libsource (lib "eagle-import") (part "C-USC1210"))
    )
    (comp (ref "CPU_PWR")
      (value "CPU PWR")
      (footprint "eagle-import:KK254_VERT_4PIN")
      (libsource (lib "eagle-import") (part "KK254_VERT_4PIN22-29-2041"))
    )
    (comp (ref "DEPTH_SENS")
      (value "Depth Sensor")
      (footprint "eagle-import:KK254_VERT_4PIN")
      (libsource (lib "eagle-import") (part "KK254_VERT_4PIN22-29-2041"))
    )
    (comp (ref "EMB_5V")
      (value "KK254_VERT_2PIN\"\"")
      (footprint "eagle-import:KK254_VERT_2PIN")
      (libsource (lib "eagle-import") (part "KK254_VERT_2PIN{dblquote}{dblquote}"))
    )
    (comp (ref "ETHERNET")
      (value "KK254_VERT_2PIN\"\"")
      (footprint "eagle-import:KK254_VERT_2PIN")
      (libsource (lib "eagle-import") (part "KK254_VERT_2PIN{dblquote}{dblquote}"))
    )
    (comp (ref "FAN1")
      (value "KK254_VERT_2PIN\"\"")
      (footprint "eagle-import:KK254_VERT_2PIN")
      (libsource (lib "eagle-import") (part "KK254_VERT_2PIN{dblquote}{dblquote}"))
    )
    (comp (ref "FAN2")
      (value "KK254_VERT_2PIN\"\"")
      (footprint "eagle-import:KK254_VERT_2PIN")
      (libsource (lib "eagle-import") (part "KK254_VERT_2PIN{dblquote}{dblquote}"))
    )
    (comp (ref "I2C")
      (value "PINHD-1X2")
      (footprint "eagle-import:1X02")
      (libsource (lib "eagle-import") (part "PINHD-1X2"))
    )
    (comp (ref "I2C_SHIFT")
      (value "PCA9306DCT")
      (footprint "eagle-import:SM8")
      (libsource (lib "eagle-import") (part "PCA9306DCT"))
    )
    (comp (ref "JP1")
      (value "JP1E")
      (footprint "eagle-import:JP1")
      (libsource (lib "eagle-import") (part "JP1E"))
    )
    (comp (ref "JP2")
      (value "JP1E")
      (footprint "eagle-import:JP1")
      (libsource (lib "eagle-import") (part "JP1E"))
    )
    (comp (ref "JP3")
      (value "PINHD-1X2")
      (footprint "eagle-import:1X02")
      (libsource (lib "eagle-import") (part "PINHD-1X2"))
    )
    (comp (ref "JP4")
      (value "PINHD-1X2")
      (footprint "eagle-import:1X02")
      (libsource (lib "eagle-import") (part "PINHD-1X2"))
    )
    (comp (ref "LED1")
      (value "Red")
      (footprint "eagle-import:0805")
      (libsource (lib "eagle-import") (part "0805_LED"))
    )
    (comp (ref "LED3")
      (value "Red")
      (footprint "eagle-import:0805")
      (libsource (lib "eagle-import") (part "0805_LED"))
    )
    (comp (ref "LED4")
      (value "Green")
      (footprint "eagle-import:CHIPLED_0805")
      (libsource (lib "eagle-import") (part "LEDCHIPLED_0805"))
    )
    (comp (ref "LED5")
      (value "Green")
      (footprint "eagle-import:0805")
      (libsource (lib "eagle-import") (part "0805_LED"))
    )
    (comp (ref "LED6")
      (value "Yellow")
      (footprint "eagle-import:0805")
      (libsource (lib "eagle-import") (part "0805_LED"))
    )
    (comp (ref "LED7")
      (value "Yellow")
      (footprint "eagle-import:0805")
      (libsource (lib "eagle-import") (part "0805_LED"))
    )
    (comp (ref "LED8")
      (value "Green")
      (footprint "eagle-import:0805")
      (libsource (lib "eagle-import") (part "0805_LED"))
    )
    (comp (ref "LED9")
      (value "Green")
      (footprint "eagle-import:0805")
      (libsource (lib "eagle-import") (part "0805_LED"))
    )
    (comp (ref "PMOS1")
      (value "SSM3J353F")
      (footprint "eagle-import:SOT-346-3_S-MINI")
      (libsource (lib "eagle-import") (part "SSM3J353F"))
    )
    (comp (ref "PMOS2")
      (value "SSM3J353F")
      (footprint "eagle-import:SOT-346-3_S-MINI")
      (libsource (lib "eagle-import") (part "SSM3J353F"))
    )
    (comp (ref "R1")
      (value "200k")
      (footprint "eagle-import:R0805")
      (libsource (lib "eagle-import") (part "R-US_R0805"))
    )
    (comp (ref "R2")
      (value "R-TRIMM3314J")
      (footprint "eagle-import:RTRIM3314J")
      (libsource (lib "eagle-import") (part "R-TRIMM3314J"))
    )
    (comp (ref "R3")
      (value "R-TRIMM3314J")
      (footprint "eagle-import:RTRIM3314J")
      (libsource (lib "eagle-import") (part "R-TRIMM3314J"))
    )
    (comp (ref "R4")
      (value "10k")
      (footprint "eagle-import:R0805")
      (libsource (lib "eagle-import") (part "R-US_R0805"))
    )
    (comp (ref "R5")
      (value "21kO")
      (footprint "eagle-import:RC55")
      (libsource (lib "eagle-import") (part "R-US_RC55/H8"))
    )
    (comp (ref "R6")
      (value "2.61kO")
      (footprint "eagle-import:RC55")
      (libsource (lib "eagle-import") (part "R-US_RC55/H8"))
    )
    (comp (ref "R7")
      (value "4.7k")
      (footprint "eagle-import:R0805")
      (libsource (lib "eagle-import") (part "R-US_R0805"))
    )
    (comp (ref "R8")
      (value "4.7k")
      (footprint "eagle-import:R0805")
      (libsource (lib "eagle-import") (part "R-US_R0805"))
    )
    (comp (ref "R9")
      (value "12k")
      (footprint "eagle-import:R0805")
      (libsource (lib "eagle-import") (part "R-US_R0805"))
    )
    (comp (ref "R10")
      (value "4.3k")
      (footprint "eagle-import:R0805")
      (libsource (lib "eagle-import") (part "R-US_R0805"))
    )
    (comp (ref "R11")
      (value "4.3k")
      (footprint "eagle-import:R0805")
      (libsource (lib "eagle-import") (part "R-US_R0805"))
    )
    (comp (ref "R12")
      (value "5m")
      (footprint "eagle-import:R0805")
      (libsource (lib "eagle-import") (part "R-US_R0805"))
    )
    (comp (ref "R13")
      (value "20.8k")
      (footprint "eagle-import:R0805")
      (libsource (lib "eagle-import") (part "R-US_R0805"))
    )
    (comp (ref "R14")
      (value "51k")
      (footprint "eagle-import:R0805")
      (libsource (lib "eagle-import") (part "R-US_R0805"))
    )
    (comp (ref "R15")
      (value "5m")
      (footprint "eagle-import:R0805")
      (libsource (lib "eagle-import") (part "R-US_R0805"))
    )
    (comp (ref "R16")
      (value "10\\")
      (footprint "eagle-import:R0805")
      (libsource (lib "eagle-import") (part "R-US_R0805"))
    )
    (comp (ref "R17")
      (value "200k")
      (footprint "eagle-import:R0805")
      (libsource (lib "eagle-import") (part "R-US_R0805"))
    )
    (comp (ref "R19")
      (value "8.2k")
      (footprint "eagle-import:R0805")
      (libsource (lib "eagle-import") (part "R-US_R0805"))
    )
    (comp (ref "R20")
      (value "5.1k")
      (footprint "eagle-import:R0805")
      (libsource (lib "eagle-import") (part "R-US_R0805"))
    )
    (comp (ref "R22")
      (value "510")
      (footprint "eagle-import:R0805")
      (libsource (lib "eagle-import") (part "R-US_R0805"))
    )
    (comp (ref "R23")
      (value "51k")
      (footprint "eagle-import:R0805")
      (libsource (lib "eagle-import") (part "R-US_R0805"))
    )
    (comp (ref "R24")
      (value "5.1k")
      (footprint "eagle-import:R0805")
      (libsource (lib "eagle-import") (part "R-US_R0805"))
    )
    (comp (ref "R25")
      (value "10")
      (footprint "eagle-import:R0805")
      (libsource (lib "eagle-import") (part "R-US_R0805"))
    )
    (comp (ref "R26")
      (value "10\\")
      (footprint "eagle-import:R0805")
      (libsource (lib "eagle-import") (part "R-US_R0805"))
    )
    (comp (ref "R27")
      (value "200k")
      (footprint "eagle-import:R0805")
      (libsource (lib "eagle-import") (part "R-US_R0805"))
    )
    (comp (ref "R28")
      (value "8.2k")
      (footprint "eagle-import:R0805")
      (libsource (lib "eagle-import") (part "R-US_R0805"))
    )
    (comp (ref "R29")
      (value "6.8k")
      (footprint "eagle-import:R0805")
      (libsource (lib "eagle-import") (part "R-US_R0805"))
    )
    (comp (ref "R30")
      (value "10")
      (footprint "eagle-import:R0805")
      (libsource (lib "eagle-import") (part "R-US_R0805"))
    )
    (comp (ref "R31")
      (value "270")
      (footprint "eagle-import:R0805")
      (libsource (lib "eagle-import") (part "R-US_R0805"))
    )
    (comp (ref "R32")
      (value "1.5k")
      (footprint "eagle-import:R0805")
      (libsource (lib "eagle-import") (part "R-US_R0805"))
    )
    (comp (ref "R33")
      (value "1.2k")
      (footprint "eagle-import:R0805")
      (libsource (lib "eagle-import") (part "R-US_R0805"))
    )
    (comp (ref "R34")
      (value "68")
      (footprint "eagle-import:R0805")
      (libsource (lib "eagle-import") (part "R-US_R0805"))
    )
    (comp (ref "R35")
      (value "10")
      (footprint "eagle-import:R0805")
      (libsource (lib "eagle-import") (part "R-US_R0805"))
    )
    (comp (ref "R36")
      (value "1MO")
      (footprint "eagle-import:R0805")
      (libsource (lib "eagle-import") (part "R-US_R0805"))
    )
    (comp (ref "R39")
      (value "~3k")
      (footprint "eagle-import:R0805")
      (libsource (lib "eagle-import") (part "R-US_R0805"))
    )
    (comp (ref "R41")
      (value "1MO")
      (footprint "eagle-import:R0805")
      (libsource (lib "eagle-import") (part "R-US_R0805"))
    )
    (comp (ref "R43")
      (value "~3k")
      (footprint "eagle-import:R0805")
      (libsource (lib "eagle-import") (part "R-US_R0805"))
    )
    (comp (ref "R44")
      (value "1.2k")
      (footprint "eagle-import:R0805")
      (libsource (lib "eagle-import") (part "R-US_R0805"))
    )
    (comp (ref "R45")
      (value "1MO")
      (footprint "eagle-import:R0805")
      (libsource (lib "eagle-import") (part "R-US_R0805"))
    )
    (comp (ref "R46")
      (value "1.2k")
      (footprint "eagle-import:R0805")
      (libsource (lib "eagle-import") (part "R-US_R0805"))
    )
    (comp (ref "R47")
      (value "1MO")
      (footprint "eagle-import:R0805")
      (libsource (lib "eagle-import") (part "R-US_R0805"))
    )
    (comp (ref "R48")
      (value "330")
      (footprint "eagle-import:R0805")
      (libsource (lib "eagle-import") (part "R-US_R0805"))
    )
    (comp (ref "R49")
      (value "330")
      (footprint "eagle-import:R0805")
      (libsource (lib "eagle-import") (part "R-US_R0805"))
    )
    (comp (ref "R50")
      (value "1.5k")
      (footprint "eagle-import:R0805")
      (libsource (lib "eagle-import") (part "R-US_R0805"))
    )
    (comp (ref "R51")
      (value "1.5k")
      (footprint "eagle-import:R0805")
      (libsource (lib "eagle-import") (part "R-US_R0805"))
    )
    (comp (ref "SHDN_JMP")
      (value "PINHD-1X2")
      (footprint "eagle-import:1X02")
      (libsource (lib "eagle-import") (part "PINHD-1X2"))
    )
    (comp (ref "SHDN_SW")
      (value "PINHD-1X2")
      (footprint "eagle-import:1X02")
      (libsource (lib "eagle-import") (part "PINHD-1X2"))
    )
    (comp (ref "SHORE_IN")
      (value "2_SUPERSABRE")
      (footprint "eagle-import:SUPERSABRE_2CIRCUIT")
      (libsource (lib "eagle-import") (part "2_SUPERSABRE"))
    )
    (comp (ref "THRUST1")
      (value "KK254_VERT_4PIN22-29-2041")
      (footprint "eagle-import:KK254_VERT_4PIN")
      (libsource (lib "eagle-import") (part "KK254_VERT_4PIN22-29-2041"))
    )
    (comp (ref "THRUST2")
      (value "KK254_VERT_4PIN22-29-2041")
      (footprint "eagle-import:KK254_VERT_4PIN")
      (libsource (lib "eagle-import") (part "KK254_VERT_4PIN22-29-2041"))
    )
    (comp (ref "THRUST3")
      (value "KK254_VERT_4PIN22-29-2041")
      (footprint "eagle-import:KK254_VERT_4PIN")
      (libsource (lib "eagle-import") (part "KK254_VERT_4PIN22-29-2041"))
    )
    (comp (ref "THRUST4")
      (value "KK254_VERT_4PIN22-29-2041")
      (footprint "eagle-import:KK254_VERT_4PIN")
      (libsource (lib "eagle-import") (part "KK254_VERT_4PIN22-29-2041"))
    )
    (comp (ref "THRUST5")
      (value "KK254_VERT_4PIN22-29-2041")
      (footprint "eagle-import:KK254_VERT_4PIN")
      (libsource (lib "eagle-import") (part "KK254_VERT_4PIN22-29-2041"))
    )
    (comp (ref "THRUST6")
      (value "KK254_VERT_4PIN22-29-2041")
      (footprint "eagle-import:KK254_VERT_4PIN")
      (libsource (lib "eagle-import") (part "KK254_VERT_4PIN22-29-2041"))
    )
    (comp (ref "THRUST7")
      (value "KK254_VERT_4PIN22-29-2041")
      (footprint "eagle-import:KK254_VERT_4PIN")
      (libsource (lib "eagle-import") (part "KK254_VERT_4PIN22-29-2041"))
    )
    (comp (ref "THRUST8")
      (value "KK254_VERT_4PIN22-29-2041")
      (footprint "eagle-import:KK254_VERT_4PIN")
      (libsource (lib "eagle-import") (part "KK254_VERT_4PIN22-29-2041"))
    )
    (comp (ref "THRUSTER_CURR_ADC")
      (value "ADS7828")
      (footprint "eagle-import:TSSOP16")
      (libsource (lib "eagle-import") (part "ADS7828"))
    )
    (comp (ref "U$1")
      (value "NCP1117")
      (footprint "eagle-import:SOT-223")
      (libsource (lib "eagle-import") (part "NCP1117"))
    )
    (comp (ref "U$2")
      (value "ACS713SOIC")
      (footprint "eagle-import:ACS713-SOIC")
      (libsource (lib "eagle-import") (part "ACS713SOIC"))
    )
    (comp (ref "U$3")
      (value "TEST_PT534-5004")
      (footprint "eagle-import:534-5004")
      (libsource (lib "eagle-import") (part "TEST_PT534-5004"))
    )
    (comp (ref "U$4")
      (value "ACS713SOIC")
      (footprint "eagle-import:ACS713-SOIC")
      (libsource (lib "eagle-import") (part "ACS713SOIC"))
    )
    (comp (ref "U$5")
      (value "25A Fuse")
      (footprint "eagle-import:1.25__FUSECLIPS")
      (libsource (lib "eagle-import") (part "BOWED-1.25{dblquote}-FUSECLIPS"))
    )
    (comp (ref "U$6")
      (value "4A Fuse")
      (footprint "eagle-import:154-OMNI-BLOK")
      (libsource (lib "eagle-import") (part "154-OMNI_BLOK"))
    )
    (comp (ref "U$7")
      (value "KUHP-5XX1-XX")
      (footprint "eagle-import:KUHP_6.35MM-QUICK-CONNECT")
      (libsource (lib "eagle-import") (part "KUHP-5XX1-XX"))
    )
    (comp (ref "U$8")
      (value "ACS713SOIC")
      (footprint "eagle-import:ACS713-SOIC")
      (libsource (lib "eagle-import") (part "ACS713SOIC"))
    )
    (comp (ref "U$9")
      (value "4A Fuse")
      (footprint "eagle-import:154-OMNI-BLOK")
      (libsource (lib "eagle-import") (part "154-OMNI_BLOK"))
    )
    (comp (ref "U$10")
      (value "VTVSDO-219AB")
      (footprint "eagle-import:DO-219AB")
      (libsource (lib "eagle-import") (part "VTVSDO-219AB"))
    )
    (comp (ref "U$11")
      (value "ACS713SOIC")
      (footprint "eagle-import:ACS713-SOIC")
      (libsource (lib "eagle-import") (part "ACS713SOIC"))
    )
    (comp (ref "U$12")
      (value "4A Fuse")
      (footprint "eagle-import:154-OMNI-BLOK")
      (libsource (lib "eagle-import") (part "154-OMNI_BLOK"))
    )
    (comp (ref "U$13")
      (value "VTVSDO-219AB")
      (footprint "eagle-import:DO-219AB")
      (libsource (lib "eagle-import") (part "VTVSDO-219AB"))
    )
    (comp (ref "U$14")
      (value "ACS713SOIC")
      (footprint "eagle-import:ACS713-SOIC")
      (libsource (lib "eagle-import") (part "ACS713SOIC"))
    )
    (comp (ref "U$15")
      (value "4A Fuse")
      (footprint "eagle-import:154-OMNI-BLOK")
      (libsource (lib "eagle-import") (part "154-OMNI_BLOK"))
    )
    (comp (ref "U$16")
      (value "VTVSDO-219AB")
      (footprint "eagle-import:DO-219AB")
      (libsource (lib "eagle-import") (part "VTVSDO-219AB"))
    )
    (comp (ref "U$17")
      (value "ACS713SOIC")
      (footprint "eagle-import:ACS713-SOIC")
      (libsource (lib "eagle-import") (part "ACS713SOIC"))
    )
    (comp (ref "U$18")
      (value "4A Fuse")
      (footprint "eagle-import:154-OMNI-BLOK")
      (libsource (lib "eagle-import") (part "154-OMNI_BLOK"))
    )
    (comp (ref "U$19")
      (value "ACS713SOIC")
      (footprint "eagle-import:ACS713-SOIC")
      (libsource (lib "eagle-import") (part "ACS713SOIC"))
    )
    (comp (ref "U$20")
      (value "4A Fuse")
      (footprint "eagle-import:154-OMNI-BLOK")
      (libsource (lib "eagle-import") (part "154-OMNI_BLOK"))
    )
    (comp (ref "U$21")
      (value "VTVSSOT323")
      (footprint "eagle-import:SOT323-R")
      (libsource (lib "eagle-import") (part "VTVSSOT323"))
    )
    (comp (ref "U$22")
      (value "VTVSDO-219AB")
      (footprint "eagle-import:DO-219AB")
      (libsource (lib "eagle-import") (part "VTVSDO-219AB"))
    )
    (comp (ref "U$23")
      (value "ACS713SOIC")
      (footprint "eagle-import:ACS713-SOIC")
      (libsource (lib "eagle-import") (part "ACS713SOIC"))
    )
    (comp (ref "U$24")
      (value "BTS5090-1EJA")
      (footprint "eagle-import:SOIC8+PAD")
      (libsource (lib "eagle-import") (part "BTS5090-1EJA"))
    )
    (comp (ref "U$25")
      (value "PTN78020")
      (footprint "eagle-import:PTN")
      (libsource (lib "eagle-import") (part "PTN78020"))
    )
    (comp (ref "U$26")
      (value "VTVSDO-219AB")
      (footprint "eagle-import:DO-219AB")
      (libsource (lib "eagle-import") (part "VTVSDO-219AB"))
    )
    (comp (ref "U$27")
      (value "4A Fuse")
      (footprint "eagle-import:154-OMNI-BLOK")
      (libsource (lib "eagle-import") (part "154-OMNI_BLOK"))
    )
    (comp (ref "U$28")
      (value "VTVSDO-219AB")
      (footprint "eagle-import:DO-219AB")
      (libsource (lib "eagle-import") (part "VTVSDO-219AB"))
    )
    (comp (ref "U$29")
      (value "ACS713SOIC")
      (footprint "eagle-import:ACS713-SOIC")
      (libsource (lib "eagle-import") (part "ACS713SOIC"))
    )
    (comp (ref "U$30")
      (value "VTVSDO-219AB")
      (footprint "eagle-import:DO-219AB")
      (libsource (lib "eagle-import") (part "VTVSDO-219AB"))
    )
    (comp (ref "U$31")
      (value "VTVSDO-219AB")
      (footprint "eagle-import:DO-219AB")
      (libsource (lib "eagle-import") (part "VTVSDO-219AB"))
    )
    (comp (ref "U$32")
      (value "VTVSDO-219AB")
      (footprint "eagle-import:DO-219AB")
      (libsource (lib "eagle-import") (part "VTVSDO-219AB"))
    )
    (comp (ref "U$33")
      (value "VTVSDO-219AB")
      (footprint "eagle-import:DO-219AB")
      (libsource (lib "eagle-import") (part "VTVSDO-219AB"))
    )
    (comp (ref "U$34")
      (value "VTVSDO-219AB")
      (footprint "eagle-import:DO-219AB")
      (libsource (lib "eagle-import") (part "VTVSDO-219AB"))
    )
    (comp (ref "U$35")
      (value "ACS713SOIC")
      (footprint "eagle-import:ACS713-SOIC")
      (libsource (lib "eagle-import") (part "ACS713SOIC"))
    )
    (comp (ref "U$36")
      (value "4A Fuse")
      (footprint "eagle-import:154-OMNI-BLOK")
      (libsource (lib "eagle-import") (part "154-OMNI_BLOK"))
    )
    (comp (ref "U$37")
      (value "4A Fuse")
      (footprint "eagle-import:154-OMNI-BLOK")
      (libsource (lib "eagle-import") (part "154-OMNI_BLOK"))
    )
    (comp (ref "U$38")
      (value "ARDUINO_UNO")
      (footprint "eagle-import:ARDUINO_UNO")
      (libsource (lib "eagle-import") (part "ARDUINO_UNO"))
    )
    (comp (ref "U$39")
      (value "ACS713SOIC")
      (footprint "eagle-import:ACS713-SOIC")
      (libsource (lib "eagle-import") (part "ACS713SOIC"))
    )
    (comp (ref "U$40")
      (value "4A Fuse")
      (footprint "eagle-import:154-OMNI-BLOK")
      (libsource (lib "eagle-import") (part "154-OMNI_BLOK"))
    )
    (comp (ref "U$41")
      (value "PTN78020")
      (footprint "eagle-import:PTN")
      (libsource (lib "eagle-import") (part "PTN78020"))
    )
    (comp (ref "U$42")
      (value "VTVSSOT323")
      (footprint "eagle-import:SOT323-R")
      (libsource (lib "eagle-import") (part "VTVSSOT323"))
    )
    (comp (ref "U$43")
      (value "VTVSSOT323")
      (footprint "eagle-import:SOT323-R")
      (libsource (lib "eagle-import") (part "VTVSSOT323"))
    )
    (comp (ref "U$44")
      (value "VTVSSOT323")
      (footprint "eagle-import:SOT323-R")
      (libsource (lib "eagle-import") (part "VTVSSOT323"))
    )
    (comp (ref "U$45")
      (value "VTVSDO-219AB")
      (footprint "eagle-import:DO-219AB")
      (libsource (lib "eagle-import") (part "VTVSDO-219AB"))
    )
    (comp (ref "U$46")
      (value "VTVSSOT323")
      (footprint "eagle-import:SOT323-R")
      (libsource (lib "eagle-import") (part "VTVSSOT323"))
    )
    (comp (ref "U$47")
      (value "VTVSSOT323")
      (footprint "eagle-import:SOT323-R")
      (libsource (lib "eagle-import") (part "VTVSSOT323"))
    )
    (comp (ref "U$48")
      (value "LTC4364MSOP")
      (footprint "eagle-import:MSOP16")
      (libsource (lib "eagle-import") (part "LTC4364MSOP"))
    )
    (comp (ref "U$49")
      (value "STD95N2LH5")
      (footprint "eagle-import:DPAK")
      (libsource (lib "eagle-import") (part "STD95N2LH5"))
    )
    (comp (ref "U$50")
      (value "STD95N2LH5")
      (footprint "eagle-import:DPAK")
      (libsource (lib "eagle-import") (part "STD95N2LH5"))
    )
    (comp (ref "U$51")
      (value "LTC4364MSOP")
      (footprint "eagle-import:MSOP16")
      (libsource (lib "eagle-import") (part "LTC4364MSOP"))
    )
    (comp (ref "U$52")
      (value "STD95N2LH5")
      (footprint "eagle-import:DPAK")
      (libsource (lib "eagle-import") (part "STD95N2LH5"))
    )
    (comp (ref "U$53")
      (value "STD95N2LH5")
      (footprint "eagle-import:DPAK")
      (libsource (lib "eagle-import") (part "STD95N2LH5"))
    )
    (comp (ref "U$54")
      (value "TEST_PT534-5004")
      (footprint "eagle-import:534-5004")
      (libsource (lib "eagle-import") (part "TEST_PT534-5004"))
    )
    (comp (ref "U$55")
      (value "BSS138CT-NDSOT23")
      (footprint "eagle-import:SOT23")
      (libsource (lib "eagle-import") (part "BSS138CT-NDSOT23"))
    )
    (comp (ref "U$56")
      (value "74LVC1G14")
      (footprint "eagle-import:TSSOP5")
      (libsource (lib "eagle-import") (part "74LVC1G14"))
    )
    (comp (ref "U$57")
      (value "NCP1117")
      (footprint "eagle-import:SOT-223")
      (libsource (lib "eagle-import") (part "NCP1117"))
    )
    (comp (ref "U$58")
      (value "BSS138CT-NDSOT23")
      (footprint "eagle-import:SOT23")
      (libsource (lib "eagle-import") (part "BSS138CT-NDSOT23"))
    )
    (comp (ref "U$59")
      (value "TEST_PT534-5004")
      (footprint "eagle-import:534-5004")
      (libsource (lib "eagle-import") (part "TEST_PT534-5004"))
    )
    (comp (ref "U$60")
      (value "TL431DBZ")
      (footprint "eagle-import:SOT-23-3")
      (libsource (lib "eagle-import") (part "TL431DBZ"))
    )
    (comp (ref "U$61")
      (value "TL431DBZ")
      (footprint "eagle-import:SOT-23-3")
      (libsource (lib "eagle-import") (part "TL431DBZ"))
    )
    (comp (ref "U$62")
      (value "VTVSSOT323")
      (footprint "eagle-import:SOT323-R")
      (libsource (lib "eagle-import") (part "VTVSSOT323"))
    )
    (comp (ref "U$63")
      (value "VTVSDO-219AB")
      (footprint "eagle-import:DO-219AB")
      (libsource (lib "eagle-import") (part "VTVSDO-219AB"))
    )
    (comp (ref "U$64")
      (value "VTVSDO-219AB")
      (footprint "eagle-import:DO-219AB")
      (libsource (lib "eagle-import") (part "VTVSDO-219AB"))
    )
    (comp (ref "U$65")
      (value "TEST_PT534-5004")
      (footprint "eagle-import:534-5004")
      (libsource (lib "eagle-import") (part "TEST_PT534-5004"))
    )
    (comp (ref "U$66")
      (value "VTVSDO-219AB")
      (footprint "eagle-import:DO-219AB")
      (libsource (lib "eagle-import") (part "VTVSDO-219AB"))
    )
    (comp (ref "U$67")
      (value "VTVSDO-219AB")
      (footprint "eagle-import:DO-219AB")
      (libsource (lib "eagle-import") (part "VTVSDO-219AB"))
    )
    (comp (ref "U$68")
      (value "VTVSDO-219AB")
      (footprint "eagle-import:DO-219AB")
      (libsource (lib "eagle-import") (part "VTVSDO-219AB"))
    )
    (comp (ref "U$69")
      (value "TEST_PT534-5004")
      (footprint "eagle-import:534-5004")
      (libsource (lib "eagle-import") (part "TEST_PT534-5004"))
    )
    (comp (ref "U$70")
      (value "TEST_PT534-5004")
      (footprint "eagle-import:534-5004")
      (libsource (lib "eagle-import") (part "TEST_PT534-5004"))
    )
    (comp (ref "U$71")
      (value "TEST_PT534-5004")
      (footprint "eagle-import:534-5004")
      (libsource (lib "eagle-import") (part "TEST_PT534-5004"))
    )
    (comp (ref "U$72")
      (value "TEST_PT534-5004")
      (footprint "eagle-import:534-5004")
      (libsource (lib "eagle-import") (part "TEST_PT534-5004"))
    )
    (comp (ref "U$73")
      (value "TEST_PT534-5004")
      (footprint "eagle-import:534-5004")
      (libsource (lib "eagle-import") (part "TEST_PT534-5004"))
    )
    (comp (ref "U$74")
      (value "TEST_PT534-5004")
      (footprint "eagle-import:534-5004")
      (libsource (lib "eagle-import") (part "TEST_PT534-5004"))
    )
    (comp (ref "U$75")
      (value "TEST_PT534-5004")
      (footprint "eagle-import:534-5004")
      (libsource (lib "eagle-import") (part "TEST_PT534-5004"))
    )
    (comp (ref "U1")
      (value "PCA9685")
      (footprint "eagle-import:TSSOP-28_4MM")
      (libsource (lib "eagle-import") (part "PCA9685"))
    )
    (comp (ref "V-THRUST_CURR_ADC")
      (value "ADC121C021")
      (footprint "eagle-import:VSSOP-8")
      (libsource (lib "eagle-import") (part "ADC121C021"))
    )
    (comp (ref "V-THRUST_LED")
      (value "0805_LED")
      (footprint "eagle-import:0805")
      (libsource (lib "eagle-import") (part "0805_LED"))
    )
    (comp (ref "V-THRUST_OUT")
      (value "Vin_OUT")
      (footprint "eagle-import:KK254_VERT_2PIN")
      (libsource (lib "eagle-import") (part "KK254_VERT_2PIN{dblquote}{dblquote}"))
    )
    (comp (ref "V-THRUST_VOLTAGE")
      (value "INA219SOT23")
      (footprint "eagle-import:SOT-23-8")
      (libsource (lib "eagle-import") (part "INA219SOT23"))
    )
  )
  (nets
    (net (code "1") (name "+3V3") (class "Default")
      (node (ref "3V3_IN") (pin "P$1") (pinfunction "P$1_P$1") (pintype "bidirectional"))
      (node (ref "BME280") (pin "P$2") (pinfunction "~{CS}_P$2") (pintype "bidirectional"))
      (node (ref "BME280") (pin "P$5") (pinfunction "SDO/ADR_P$5") (pintype "bidirectional"))
      (node (ref "BME280") (pin "P$6") (pinfunction "VDDIO_P$6") (pintype "bidirectional"))
      (node (ref "BME280") (pin "P$8") (pinfunction "VDD_P$8") (pintype "bidirectional"))
      (node (ref "C83") (pin "1") (pinfunction "1_1") (pintype "passive"))
      (node (ref "C84") (pin "1") (pinfunction "1_1") (pintype "passive"))
      (node (ref "C85") (pin "1") (pinfunction "1_1") (pintype "passive"))
      (node (ref "I2C_SHIFT") (pin "P$2") (pinfunction "VREF1_P$2") (pintype "bidirectional"))
      (node (ref "R10") (pin "2") (pinfunction "2_2") (pintype "passive"))
      (node (ref "R11") (pin "2") (pinfunction "2_2") (pintype "passive"))
      (node (ref "R34") (pin "2") (pinfunction "2_2") (pintype "passive"))
      (node (ref "U$3") (pin "P$1") (pinfunction "1_P$1") (pintype "bidirectional"))
    )
    (net (code "2") (name "+5V") (class "Default")
      (node (ref "12V_CURR_ADC") (pin "P$5") (pinfunction "VDD_P$5") (pintype "bidirectional"))
      (node (ref "12V_VOLTAGE") (pin "P$4") (pinfunction "VS_P$4") (pintype "bidirectional"))
      (node (ref "12V_VOLTAGE") (pin "P$8") (pinfunction "A1_P$8") (pintype "bidirectional"))
      (node (ref "5V_CURR_ADC") (pin "P$5") (pinfunction "VDD_P$5") (pintype "bidirectional"))
      (node (ref "5V_CURR_ADC") (pin "P$6") (pinfunction "ADR1_P$6") (pintype "bidirectional"))
      (node (ref "5V_OUT") (pin "P$1") (pinfunction "P$1_P$1") (pintype "bidirectional"))
      (node (ref "5V_VOLTAGE") (pin "P$4") (pinfunction "VS_P$4") (pintype "bidirectional"))
      (node (ref "C1") (pin "1") (pinfunction "1_1") (pintype "passive"))
      (node (ref "C103") (pin "1") (pinfunction "1_1") (pintype "passive"))
      (node (ref "C106") (pin "1") (pinfunction "1_1") (pintype "passive"))
      (node (ref "C109") (pin "1") (pinfunction "1_1") (pintype "passive"))
      (node (ref "C11") (pin "1") (pinfunction "1_1") (pintype "passive"))
      (node (ref "C112") (pin "1") (pinfunction "1_1") (pintype "passive"))
      (node (ref "C13") (pin "1") (pinfunction "1_1") (pintype "passive"))
      (node (ref "C14") (pin "1") (pinfunction "1_1") (pintype "passive"))
      (node (ref "C19") (pin "1") (pinfunction "1_1") (pintype "passive"))
      (node (ref "C2") (pin "1") (pinfunction "1_1") (pintype "passive"))
      (node (ref "C48") (pin "1") (pinfunction "1_1") (pintype "passive"))
      (node (ref "C5") (pin "1") (pinfunction "1_1") (pintype "passive"))
      (node (ref "C53") (pin "1") (pinfunction "1_1") (pintype "passive"))
      (node (ref "C59") (pin "1") (pinfunction "1_1") (pintype "passive"))
      (node (ref "C64") (pin "1") (pinfunction "1_1") (pintype "passive"))
      (node (ref "C66") (pin "1") (pinfunction "1_1") (pintype "passive"))
      (node (ref "C69") (pin "1") (pinfunction "1_1") (pintype "passive"))
      (node (ref "C7") (pin "1") (pinfunction "1_1") (pintype "passive"))
      (node (ref "C70") (pin "1") (pinfunction "1_1") (pintype "passive"))
      (node (ref "C71") (pin "1") (pinfunction "1_1") (pintype "passive"))
      (node (ref "C72") (pin "1") (pinfunction "1_1") (pintype "passive"))
      (node (ref "C73") (pin "1") (pinfunction "1_1") (pintype "passive"))
      (node (ref "C79") (pin "1") (pinfunction "1_1") (pintype "passive"))
      (node (ref "C8") (pin "1") (pinfunction "1_1") (pintype "passive"))
      (node (ref "C81") (pin "1") (pinfunction "1_1") (pintype "passive"))
      (node (ref "C82") (pin "1") (pinfunction "1_1") (pintype "passive"))
      (node (ref "C93") (pin "1") (pinfunction "1_1") (pintype "passive"))
      (node (ref "C94") (pin "1") (pinfunction "1_1") (pintype "passive"))
      (node (ref "DEPTH_SENS") (pin "P$4") (pinfunction "P$4_P$4") (pintype "bidirectional"))
      (node (ref "EMB_5V") (pin "P$1") (pinfunction "P$1_P$1") (pintype "bidirectional"))
      (node (ref "ETHERNET") (pin "P$1") (pinfunction "P$1_P$1") (pintype "bidirectional"))
      (node (ref "FAN1") (pin "P$1") (pinfunction "P$1_P$1") (pintype "bidirectional"))
      (node (ref "FAN2") (pin "P$1") (pinfunction "P$1_P$1") (pintype "bidirectional"))
      (node (ref "R1") (pin "2") (pinfunction "2_2") (pintype "passive"))
      (node (ref "R31") (pin "2") (pinfunction "2_2") (pintype "passive"))
      (node (ref "R35") (pin "1") (pinfunction "1_1") (pintype "passive"))
      (node (ref "R7") (pin "2") (pinfunction "2_2") (pintype "passive"))
      (node (ref "R8") (pin "2") (pinfunction "2_2") (pintype "passive"))
      (node (ref "THRUSTER_CURR_ADC") (pin "10") (pinfunction "REF_10") (pintype "bidirectional"))
      (node (ref "THRUSTER_CURR_ADC") (pin "16") (pinfunction "VDD_16") (pintype "bidirectional"))
      (node (ref "U$11") (pin "P$8") (pinfunction "VCC_P$8") (pintype "bidirectional"))
      (node (ref "U$14") (pin "P$8") (pinfunction "VCC_P$8") (pintype "bidirectional"))
      (node (ref "U$17") (pin "P$8") (pinfunction "VCC_P$8") (pintype "bidirectional"))
      (node (ref "U$19") (pin "P$8") (pinfunction "VCC_P$8") (pintype "bidirectional"))
      (node (ref "U$2") (pin "P$8") (pinfunction "VCC_P$8") (pintype "bidirectional"))
      (node (ref "U$20") (pin "P$2") (pinfunction "P$2_P$2") (pintype "bidirectional"))
      (node (ref "U$23") (pin "P$8") (pinfunction "VCC_P$8") (pintype "bidirectional"))
      (node (ref "U$29") (pin "P$8") (pinfunction "VCC_P$8") (pintype "bidirectional"))
      (node (ref "U$35") (pin "P$8") (pinfunction "VCC_P$8") (pintype "bidirectional"))
      (node (ref "U$39") (pin "P$8") (pinfunction "VCC_P$8") (pintype "bidirectional"))
      (node (ref "U$4") (pin "P$8") (pinfunction "VCC_P$8") (pintype "bidirectional"))
      (node (ref "U$42") (pin "1") (pinfunction "C_1") (pintype "passive"))
      (node (ref "U$42") (pin "2") (pinfunction "C_2") (pintype "passive"))
      (node (ref "U$43") (pin "1") (pinfunction "C_1") (pintype "passive"))
      (node (ref "U$43") (pin "2") (pinfunction "C_2") (pintype "passive"))
      (node (ref "U$44") (pin "1") (pinfunction "C_1") (pintype "passive"))
      (node (ref "U$44") (pin "2") (pinfunction "C_2") (pintype "passive"))
      (node (ref "U$46") (pin "1") (pinfunction "C_1") (pintype "passive"))
      (node (ref "U$46") (pin "2") (pinfunction "C_2") (pintype "passive"))
      (node (ref "U$47") (pin "1") (pinfunction "C_1") (pintype "passive"))
      (node (ref "U$47") (pin "2") (pinfunction "C_2") (pintype "passive"))
      (node (ref "U$69") (pin "P$1") (pinfunction "1_P$1") (pintype "bidirectional"))
      (node (ref "U$8") (pin "P$8") (pinfunction "VCC_P$8") (pintype "bidirectional"))
      (node (ref "U1") (pin "1") (pinfunction "A0_1") (pintype "bidirectional"))
      (node (ref "U1") (pin "2") (pinfunction "A1_2") (pintype "bidirectional"))
      (node (ref "U1") (pin "24") (pinfunction "A5_24") (pintype "bidirectional"))
      (node (ref "U1") (pin "28") (pinfunction "VDD_28") (pintype "bidirectional"))
      (node (ref "U1") (pin "3") (pinfunction "A2_3") (pintype "bidirectional"))
      (node (ref "U1") (pin "4") (pinfunction "A3_4") (pintype "bidirectional"))
      (node (ref "U1") (pin "5") (pinfunction "A4_5") (pintype "bidirectional"))
      (node (ref "V-THRUST_CURR_ADC") (pin "P$3") (pinfunction "ADR0_P$3") (pintype "bidirectional"))
      (node (ref "V-THRUST_CURR_ADC") (pin "P$5") (pinfunction "VDD_P$5") (pintype "bidirectional"))
      (node (ref "V-THRUST_CURR_ADC") (pin "P$6") (pinfunction "ADR1_P$6") (pintype "bidirectional"))
      (node (ref "V-THRUST_VOLTAGE") (pin "P$4") (pinfunction "VS_P$4") (pintype "bidirectional"))
      (node (ref "V-THRUST_VOLTAGE") (pin "P$7") (pinfunction "A0_P$7") (pintype "bidirectional"))
      (node (ref "V-THRUST_VOLTAGE") (pin "P$8") (pinfunction "A1_P$8") (pintype "bidirectional"))
    )
    (net (code "3") (name "+12V") (class "Default")
      (node (ref "12V_OUT") (pin "P$1") (pinfunction "P$1_P$1") (pintype "bidirectional"))
      (node (ref "C16") (pin "1") (pinfunction "1_1") (pintype "passive"))
      (node (ref "C33") (pin "1") (pinfunction "1_1") (pintype "passive"))
      (node (ref "C45") (pin "1") (pinfunction "1_1") (pintype "passive"))
      (node (ref "C49") (pin "1") (pinfunction "1_1") (pintype "passive"))
      (node (ref "C77") (pin "1") (pinfunction "1_1") (pintype "passive"))
      (node (ref "C78") (pin "1") (pinfunction "1_1") (pintype "passive"))
      (node (ref "CPU_PWR") (pin "P$3") (pinfunction "P$3_P$3") (pintype "bidirectional"))
      (node (ref "CPU_PWR") (pin "P$4") (pinfunction "P$4_P$4") (pintype "bidirectional"))
      (node (ref "JP4") (pin "1") (pinfunction "1_1") (pintype "passive"))
      (node (ref "R25") (pin "1") (pinfunction "1_1") (pintype "passive"))
      (node (ref "R33") (pin "2") (pinfunction "2_2") (pintype "passive"))
      (node (ref "U$24") (pin "PAD") (pinfunction "VS_PAD") (pintype "bidirectional"))
      (node (ref "U$36") (pin "P$2") (pinfunction "P$2_P$2") (pintype "bidirectional"))
      (node (ref "U$63") (pin "P$2") (pinfunction "C_P$2") (pintype "passive"))
      (node (ref "U$64") (pin "P$2") (pinfunction "C_P$2") (pintype "passive"))
      (node (ref "U$70") (pin "P$1") (pinfunction "1_P$1") (pintype "bidirectional"))
    )
    (net (code "4") (name "/5V") (class "Default")
      (node (ref "C36") (pin "1") (pinfunction "1_1") (pintype "passive"))
      (node (ref "C62") (pin "1") (pinfunction "1_1") (pintype "passive"))
      (node (ref "R29") (pin "2") (pinfunction "2_2") (pintype "passive"))
      (node (ref "SHDN_JMP") (pin "1") (pinfunction "1_1") (pintype "passive"))
      (node (ref "U$56") (pin "P$5") (pinfunction "VDD_P$5") (pintype "bidirectional"))
      (node (ref "U$57") (pin "P$2") (pinfunction "VOUT_P$2") (pintype "bidirectional"))
      (node (ref "U$57") (pin "P$4") (pinfunction "VOUT_P$4") (pintype "bidirectional"))
    )
    (net (code "5") (name "/SCL1") (class "Default")
      (node (ref "I2C_SHIFT") (pin "P$6") (pinfunction "SCL2_P$6") (pintype "bidirectional"))
    )
    (net (code "6") (name "/SDA1") (class "Default")
      (node (ref "I2C_SHIFT") (pin "P$5") (pinfunction "SDA2_P$5") (pintype "bidirectional"))
    )
    (net (code "7") (name "/SHDN_SW") (class "Default")
      (node (ref "R22") (pin "1") (pinfunction "1_1") (pintype "passive"))
      (node (ref "R29") (pin "1") (pinfunction "1_1") (pintype "passive"))
      (node (ref "SHDN_SW") (pin "2") (pinfunction "2_2") (pintype "passive"))
      (node (ref "U$62") (pin "1") (pinfunction "C_1") (pintype "passive"))
      (node (ref "U$62") (pin "2") (pinfunction "C_2") (pintype "passive"))
    )
    (net (code "8") (name "/T1_PWM") (class "Default")
      (node (ref "THRUST1") (pin "P$2") (pinfunction "P$2_P$2") (pintype "bidirectional"))
      (node (ref "U1") (pin "6") (pinfunction "CH0_6") (pintype "bidirectional"))
    )
    (net (code "9") (name "/T2_CURR") (class "Default")
      (node (ref "THRUSTER_CURR_ADC") (pin "2") (pinfunction "CH1_2") (pintype "bidirectional"))
      (node (ref "U$8") (pin "P$7") (pinfunction "VIOUT_P$7") (pintype "bidirectional"))
    )
    (net (code "10") (name "/T2_PWM") (class "Default")
      (node (ref "THRUST2") (pin "P$2") (pinfunction "P$2_P$2") (pintype "bidirectional"))
      (node (ref "U1") (pin "7") (pinfunction "CH1_7") (pintype "bidirectional"))
    )
    (net (code "11") (name "/T3_PWM") (class "Default")
      (node (ref "THRUST3") (pin "P$2") (pinfunction "P$2_P$2") (pintype "bidirectional"))
      (node (ref "U1") (pin "8") (pinfunction "CH2_8") (pintype "bidirectional"))
    )
    (net (code "12") (name "/T4_PWM") (class "Default")
      (node (ref "THRUST4") (pin "P$2") (pinfunction "P$2_P$2") (pintype "bidirectional"))
      (node (ref "U1") (pin "9") (pinfunction "CH3_9") (pintype "bidirectional"))
    )
    (net (code "13") (name "/T5_PWM") (class "Default")
      (node (ref "THRUST5") (pin "P$2") (pinfunction "P$2_P$2") (pintype "bidirectional"))
      (node (ref "U1") (pin "10") (pinfunction "CH4_10") (pintype "bidirectional"))
    )
    (net (code "14") (name "/T6_PWM") (class "Default")
      (node (ref "THRUST6") (pin "P$2") (pinfunction "P$2_P$2") (pintype "bidirectional"))
      (node (ref "U1") (pin "11") (pinfunction "CH5_11") (pintype "bidirectional"))
    )
    (net (code "15") (name "/T7_PWM") (class "Default")
      (node (ref "THRUST7") (pin "P$2") (pinfunction "P$2_P$2") (pintype "bidirectional"))
      (node (ref "U1") (pin "12") (pinfunction "CH6_12") (pintype "bidirectional"))
    )
    (net (code "16") (name "/T8_PWM") (class "Default")
      (node (ref "THRUST8") (pin "P$2") (pinfunction "P$2_P$2") (pintype "bidirectional"))
      (node (ref "U1") (pin "13") (pinfunction "CH7_13") (pintype "bidirectional"))
    )
    (net (code "17") (name "/V_BATT1") (class "Default")
      (node (ref "BATT1_IN") (pin "P$1") (pinfunction "P$1_P$1") (pintype "bidirectional"))
      (node (ref "C34") (pin "1") (pinfunction "1_1") (pintype "passive"))
      (node (ref "C61") (pin "1") (pinfunction "1_1") (pintype "passive"))
      (node (ref "LED4") (pin "A") (pinfunction "A_A") (pintype "passive"))
      (node (ref "PMOS2") (pin "P$3") (pinfunction "S_P$3") (pintype "bidirectional"))
      (node (ref "R27") (pin "2") (pinfunction "2_2") (pintype "passive"))
      (node (ref "R3") (pin "3") (pinfunction "A_3") (pintype "passive"))
      (node (ref "R41") (pin "2") (pinfunction "2_2") (pintype "passive"))
      (node (ref "R45") (pin "2") (pinfunction "2_2") (pintype "passive"))
      (node (ref "R49") (pin "2") (pinfunction "2_2") (pintype "passive"))
      (node (ref "R51") (pin "2") (pinfunction "2_2") (pintype "passive"))
      (node (ref "U$48") (pin "VCC") (pinfunction "VCC_VCC") (pintype "bidirectional"))
      (node (ref "U$49") (pin "TAB") (pinfunction "D_TAB") (pintype "bidirectional"))
      (node (ref "U$57") (pin "P$3") (pinfunction "VIN_P$3") (pintype "bidirectional"))
      (node (ref "U$68") (pin "P$2") (pinfunction "C_P$2") (pintype "passive"))
      (node (ref "U$75") (pin "P$1") (pinfunction "1_P$1") (pintype "bidirectional"))
    )
    (net (code "18") (name "/V_BATT2") (class "Default")
      (node (ref "BATT2_IN") (pin "P$1") (pinfunction "P$1_P$1") (pintype "bidirectional"))
      (node (ref "C35") (pin "1") (pinfunction "1_1") (pintype "passive"))
      (node (ref "LED5") (pin "P$1") (pinfunction "A_P$1") (pintype "passive"))
      (node (ref "PMOS1") (pin "P$3") (pinfunction "S_P$3") (pintype "bidirectional"))
      (node (ref "R17") (pin "2") (pinfunction "2_2") (pintype "passive"))
      (node (ref "R2") (pin "3") (pinfunction "A_3") (pintype "passive"))
      (node (ref "R36") (pin "2") (pinfunction "2_2") (pintype "passive"))
      (node (ref "R47") (pin "2") (pinfunction "2_2") (pintype "passive"))
      (node (ref "R48") (pin "2") (pinfunction "2_2") (pintype "passive"))
      (node (ref "R50") (pin "2") (pinfunction "2_2") (pintype "passive"))
      (node (ref "U$51") (pin "VCC") (pinfunction "VCC_VCC") (pintype "bidirectional"))
      (node (ref "U$52") (pin "TAB") (pinfunction "D_TAB") (pintype "bidirectional"))
      (node (ref "U$67") (pin "P$2") (pinfunction "C_P$2") (pintype "passive"))
      (node (ref "U$74") (pin "P$1") (pinfunction "1_P$1") (pintype "bidirectional"))
    )
    (net (code "19") (name "5V_CURR") (class "Default")
      (node (ref "C50") (pin "P$1") (pinfunction "+_P$1") (pintype "passive"))
      (node (ref "C51") (pin "1") (pinfunction "1_1") (pintype "passive"))
      (node (ref "U$2") (pin "P$1") (pinfunction "IP+_P$1") (pintype "bidirectional"))
      (node (ref "U$2") (pin "P$2") (pinfunction "IP+_P$2") (pintype "bidirectional"))
      (node (ref "U$25") (pin "P$5") (pinfunction "VOSENSE_P$5") (pintype "bidirectional"))
      (node (ref "U$25") (pin "P$6") (pinfunction "VO_P$6") (pintype "bidirectional"))
    )
    (net (code "20") (name "12V_CURR") (class "Default")
      (node (ref "C38") (pin "P$1") (pinfunction "+_P$1") (pintype "passive"))
      (node (ref "C40") (pin "1") (pinfunction "1_1") (pintype "passive"))
      (node (ref "U$35") (pin "P$1") (pinfunction "IP+_P$1") (pintype "bidirectional"))
      (node (ref "U$35") (pin "P$2") (pinfunction "IP+_P$2") (pintype "bidirectional"))
      (node (ref "U$41") (pin "P$5") (pinfunction "VOSENSE_P$5") (pintype "bidirectional"))
      (node (ref "U$41") (pin "P$6") (pinfunction "VO_P$6") (pintype "bidirectional"))
    )
    (net (code "21") (name "GND") (class "Default")
      (node (ref "12V_CURR_ADC") (pin "P$3") (pinfunction "ADR0_P$3") (pintype "bidirectional"))
      (node (ref "12V_CURR_ADC") (pin "P$6") (pinfunction "ADR1_P$6") (pintype "bidirectional"))
      (node (ref "12V_CURR_ADC") (pin "P$7") (pinfunction "GND_P$7") (pintype "bidirectional"))
      (node (ref "12V_LED") (pin "P$2") (pinfunction "C_P$2") (pintype "passive"))
      (node (ref "12V_OUT") (pin "P$2") (pinfunction "P$2_P$2") (pintype "bidirectional"))
      (node (ref "12V_VOLTAGE") (pin "P$3") (pinfunction "GND_P$3") (pintype "bidirectional"))
      (node (ref "12V_VOLTAGE") (pin "P$7") (pinfunction "A0_P$7") (pintype "bidirectional"))
      (node (ref "3V3_IN") (pin "P$2") (pinfunction "P$2_P$2") (pintype "bidirectional"))
      (node (ref "3V3_LED") (pin "P$2") (pinfunction "C_P$2") (pintype "passive"))
      (node (ref "5V_CURR_ADC") (pin "P$3") (pinfunction "ADR0_P$3") (pintype "bidirectional"))
      (node (ref "5V_CURR_ADC") (pin "P$7") (pinfunction "GND_P$7") (pintype "bidirectional"))
      (node (ref "5V_LED") (pin "P$2") (pinfunction "C_P$2") (pintype "passive"))
      (node (ref "5V_OUT") (pin "P$2") (pinfunction "P$2_P$2") (pintype "bidirectional"))
      (node (ref "5V_VOLTAGE") (pin "P$3") (pinfunction "GND_P$3") (pintype "bidirectional"))
      (node (ref "5V_VOLTAGE") (pin "P$7") (pinfunction "A0_P$7") (pintype "bidirectional"))
      (node (ref "5V_VOLTAGE") (pin "P$8") (pinfunction "A1_P$8") (pintype "bidirectional"))
      (node (ref "BATT1_IN") (pin "P$2") (pinfunction "P$2_P$2") (pintype "bidirectional"))
      (node (ref "BATT2_IN") (pin "P$2") (pinfunction "P$2_P$2") (pintype "bidirectional"))
      (node (ref "BME280") (pin "P$1") (pinfunction "GND1_P$1") (pintype "bidirectional"))
      (node (ref "BME280") (pin "P$7") (pinfunction "GND2_P$7") (pintype "bidirectional"))
      (node (ref "C1") (pin "2") (pinfunction "2_2") (pintype "passive"))
      (node (ref "C10") (pin "2") (pinfunction "2_2") (pintype "passive"))
      (node (ref "C101") (pin "2") (pinfunction "2_2") (pintype "passive"))
      (node (ref "C102") (pin "2") (pinfunction "2_2") (pintype "passive"))
      (node (ref "C103") (pin "2") (pinfunction "2_2") (pintype "passive"))
      (node (ref "C104") (pin "2") (pinfunction "2_2") (pintype "passive"))
      (node (ref "C105") (pin "2") (pinfunction "2_2") (pintype "passive"))
      (node (ref "C106") (pin "2") (pinfunction "2_2") (pintype "passive"))
      (node (ref "C107") (pin "2") (pinfunction "2_2") (pintype "passive"))
      (node (ref "C108") (pin "2") (pinfunction "2_2") (pintype "passive"))
      (node (ref "C109") (pin "2") (pinfunction "2_2") (pintype "passive"))
      (node (ref "C11") (pin "2") (pinfunction "2_2") (pintype "passive"))
      (node (ref "C110") (pin "2") (pinfunction "2_2") (pintype "passive"))
      (node (ref "C111") (pin "2") (pinfunction "2_2") (pintype "passive"))
      (node (ref "C112") (pin "2") (pinfunction "2_2") (pintype "passive"))
      (node (ref "C113") (pin "2") (pinfunction "2_2") (pintype "passive"))
      (node (ref "C114") (pin "2") (pinfunction "2_2") (pintype "passive"))
      (node (ref "C12") (pin "2") (pinfunction "2_2") (pintype "passive"))
      (node (ref "C13") (pin "2") (pinfunction "2_2") (pintype "passive"))
      (node (ref "C14") (pin "2") (pinfunction "2_2") (pintype "passive"))
      (node (ref "C15") (pin "2") (pinfunction "2_2") (pintype "passive"))
      (node (ref "C16") (pin "2") (pinfunction "2_2") (pintype "passive"))
      (node (ref "C17") (pin "2") (pinfunction "2_2") (pintype "passive"))
      (node (ref "C18") (pin "2") (pinfunction "2_2") (pintype "passive"))
      (node (ref "C19") (pin "2") (pinfunction "2_2") (pintype "passive"))
      (node (ref "C2") (pin "2") (pinfunction "2_2") (pintype "passive"))
      (node (ref "C20") (pin "2") (pinfunction "2_2") (pintype "passive"))
      (node (ref "C21") (pin "2") (pinfunction "2_2") (pintype "passive"))
      (node (ref "C22") (pin "2") (pinfunction "2_2") (pintype "passive"))
      (node (ref "C23") (pin "2") (pinfunction "2_2") (pintype "passive"))
      (node (ref "C27") (pin "2") (pinfunction "2_2") (pintype "passive"))
      (node (ref "C28") (pin "2") (pinfunction "2_2") (pintype "passive"))
      (node (ref "C29") (pin "2") (pinfunction "2_2") (pintype "passive"))
      (node (ref "C3") (pin "2") (pinfunction "2_2") (pintype "passive"))
      (node (ref "C30") (pin "2") (pinfunction "2_2") (pintype "passive"))
      (node (ref "C31") (pin "2") (pinfunction "2_2") (pintype "passive"))
      (node (ref "C33") (pin "2") (pinfunction "2_2") (pintype "passive"))
      (node (ref "C34") (pin "2") (pinfunction "2_2") (pintype "passive"))
      (node (ref "C35") (pin "2") (pinfunction "2_2") (pintype "passive"))
      (node (ref "C36") (pin "2") (pinfunction "2_2") (pintype "passive"))
      (node (ref "C37") (pin "2") (pinfunction "2_2") (pintype "passive"))
      (node (ref "C38") (pin "P$2") (pinfunction "-_P$2") (pintype "passive"))
      (node (ref "C4") (pin "2") (pinfunction "2_2") (pintype "passive"))
      (node (ref "C40") (pin "2") (pinfunction "2_2") (pintype "passive"))
      (node (ref "C43") (pin "-") (pinfunction "-_-") (pintype "passive"))
      (node (ref "C44") (pin "-") (pinfunction "-_-") (pintype "passive"))
      (node (ref "C45") (pin "2") (pinfunction "2_2") (pintype "passive"))
      (node (ref "C46") (pin "2") (pinfunction "2_2") (pintype "passive"))
      (node (ref "C47") (pin "2") (pinfunction "2_2") (pintype "passive"))
      (node (ref "C48") (pin "2") (pinfunction "2_2") (pintype "passive"))
      (node (ref "C49") (pin "2") (pinfunction "2_2") (pintype "passive"))
      (node (ref "C5") (pin "2") (pinfunction "2_2") (pintype "passive"))
      (node (ref "C50") (pin "P$2") (pinfunction "-_P$2") (pintype "passive"))
      (node (ref "C51") (pin "2") (pinfunction "2_2") (pintype "passive"))
      (node (ref "C53") (pin "2") (pinfunction "2_2") (pintype "passive"))
      (node (ref "C57") (pin "2") (pinfunction "2_2") (pintype "passive"))
      (node (ref "C59") (pin "2") (pinfunction "2_2") (pintype "passive"))
      (node (ref "C6") (pin "2") (pinfunction "2_2") (pintype "passive"))
      (node (ref "C60") (pin "2") (pinfunction "2_2") (pintype "passive"))
      (node (ref "C61") (pin "2") (pinfunction "2_2") (pintype "passive"))
      (node (ref "C62") (pin "2") (pinfunction "2_2") (pintype "passive"))
      (node (ref "C64") (pin "2") (pinfunction "2_2") (pintype "passive"))
      (node (ref "C65") (pin "2") (pinfunction "2_2") (pintype "passive"))
      (node (ref "C66") (pin "2") (pinfunction "2_2") (pintype "passive"))
      (node (ref "C69") (pin "2") (pinfunction "2_2") (pintype "passive"))
      (node (ref "C7") (pin "2") (pinfunction "2_2") (pintype "passive"))
      (node (ref "C70") (pin "2") (pinfunction "2_2") (pintype "passive"))
      (node (ref "C71") (pin "2") (pinfunction "2_2") (pintype "passive"))
      (node (ref "C72") (pin "2") (pinfunction "2_2") (pintype "passive"))
      (node (ref "C73") (pin "2") (pinfunction "2_2") (pintype "passive"))
      (node (ref "C74") (pin "2") (pinfunction "2_2") (pintype "passive"))
      (node (ref "C75") (pin "2") (pinfunction "2_2") (pintype "passive"))
      (node (ref "C76") (pin "2") (pinfunction "2_2") (pintype "passive"))
      (node (ref "C77") (pin "2") (pinfunction "2_2") (pintype "passive"))
      (node (ref "C78") (pin "2") (pinfunction "2_2") (pintype "passive"))
      (node (ref "C79") (pin "2") (pinfunction "2_2") (pintype "passive"))
      (node (ref "C8") (pin "2") (pinfunction "2_2") (pintype "passive"))
      (node (ref "C80") (pin "2") (pinfunction "2_2") (pintype "passive"))
      (node (ref "C81") (pin "2") (pinfunction "2_2") (pintype "passive"))
      (node (ref "C82") (pin "2") (pinfunction "2_2") (pintype "passive"))
      (node (ref "C83") (pin "2") (pinfunction "2_2") (pintype "passive"))
      (node (ref "C84") (pin "2") (pinfunction "2_2") (pintype "passive"))
      (node (ref "C85") (pin "2") (pinfunction "2_2") (pintype "passive"))
      (node (ref "C88") (pin "2") (pinfunction "2_2") (pintype "passive"))
      (node (ref "C9") (pin "2") (pinfunction "2_2") (pintype "passive"))
      (node (ref "C93") (pin "2") (pinfunction "2_2") (pintype "passive"))
      (node (ref "C94") (pin "2") (pinfunction "2_2") (pintype "passive"))
      (node (ref "CAMERA1") (pin "P$2") (pinfunction "P$2_P$2") (pintype "bidirectional"))
      (node (ref "CAMERA2") (pin "P$2") (pinfunction "P$2_P$2") (pintype "bidirectional"))
      (node (ref "CIN1") (pin "2") (pinfunction "2_2") (pintype "passive"))
      (node (ref "CIN2") (pin "2") (pinfunction "2_2") (pintype "passive"))
      (node (ref "CIN3") (pin "2") (pinfunction "2_2") (pintype "passive"))
      (node (ref "CIN4") (pin "2") (pinfunction "2_2") (pintype "passive"))
      (node (ref "CPU_PWR") (pin "P$1") (pinfunction "P$1_P$1") (pintype "bidirectional"))
      (node (ref "CPU_PWR") (pin "P$2") (pinfunction "P$2_P$2") (pintype "bidirectional"))
      (node (ref "DEPTH_SENS") (pin "P$3") (pinfunction "P$3_P$3") (pintype "bidirectional"))
      (node (ref "EMB_5V") (pin "P$2") (pinfunction "P$2_P$2") (pintype "bidirectional"))
      (node (ref "ETHERNET") (pin "P$2") (pinfunction "P$2_P$2") (pintype "bidirectional"))
      (node (ref "FAN1") (pin "P$2") (pinfunction "P$2_P$2") (pintype "bidirectional"))
      (node (ref "FAN2") (pin "P$2") (pinfunction "P$2_P$2") (pintype "bidirectional"))
      (node (ref "I2C_SHIFT") (pin "P$1") (pinfunction "GND_P$1") (pintype "bidirectional"))
      (node (ref "JP1") (pin "1") (pinfunction "1_1") (pintype "passive"))
      (node (ref "JP2") (pin "1") (pinfunction "1_1") (pintype "passive"))
      (node (ref "LED1") (pin "P$2") (pinfunction "C_P$2") (pintype "passive"))
      (node (ref "LED3") (pin "P$2") (pinfunction "C_P$2") (pintype "passive"))
      (node (ref "LED6") (pin "P$2") (pinfunction "C_P$2") (pintype "passive"))
      (node (ref "LED7") (pin "P$2") (pinfunction "C_P$2") (pintype "passive"))
      (node (ref "LED8") (pin "P$2") (pinfunction "C_P$2") (pintype "passive"))
      (node (ref "LED9") (pin "P$2") (pinfunction "C_P$2") (pintype "passive"))
      (node (ref "R13") (pin "1") (pinfunction "1_1") (pintype "passive"))
      (node (ref "R2") (pin "1") (pinfunction "E_1") (pintype "passive"))
      (node (ref "R20") (pin "1") (pinfunction "1_1") (pintype "passive"))
      (node (ref "R24") (pin "1") (pinfunction "1_1") (pintype "passive"))
      (node (ref "R3") (pin "1") (pinfunction "E_1") (pintype "passive"))
      (node (ref "R4") (pin "1") (pinfunction "1_1") (pintype "passive"))
      (node (ref "R5") (pin "P$2") (pinfunction "2_P$2") (pintype "passive"))
      (node (ref "R6") (pin "P$2") (pinfunction "2_P$2") (pintype "passive"))
      (node (ref "R9") (pin "1") (pinfunction "1_1") (pintype "passive"))
      (node (ref "SHDN_SW") (pin "1") (pinfunction "1_1") (pintype "passive"))
      (node (ref "SHORE_IN") (pin "P$2") (pinfunction "P$2_P$2") (pintype "bidirectional"))
      (node (ref "THRUST1") (pin "P$1") (pinfunction "P$1_P$1") (pintype "bidirectional"))
      (node (ref "THRUST1") (pin "P$3") (pinfunction "P$3_P$3") (pintype "bidirectional"))
      (node (ref "THRUST2") (pin "P$1") (pinfunction "P$1_P$1") (pintype "bidirectional"))
      (node (ref "THRUST2") (pin "P$3") (pinfunction "P$3_P$3") (pintype "bidirectional"))
      (node (ref "THRUST3") (pin "P$1") (pinfunction "P$1_P$1") (pintype "bidirectional"))
      (node (ref "THRUST3") (pin "P$3") (pinfunction "P$3_P$3") (pintype "bidirectional"))
      (node (ref "THRUST4") (pin "P$1") (pinfunction "P$1_P$1") (pintype "bidirectional"))
      (node (ref "THRUST4") (pin "P$3") (pinfunction "P$3_P$3") (pintype "bidirectional"))
      (node (ref "THRUST5") (pin "P$1") (pinfunction "P$1_P$1") (pintype "bidirectional"))
      (node (ref "THRUST5") (pin "P$3") (pinfunction "P$3_P$3") (pintype "bidirectional"))
      (node (ref "THRUST6") (pin "P$1") (pinfunction "P$1_P$1") (pintype "bidirectional"))
      (node (ref "THRUST6") (pin "P$3") (pinfunction "P$3_P$3") (pintype "bidirectional"))
      (node (ref "THRUST7") (pin "P$1") (pinfunction "P$1_P$1") (pintype "bidirectional"))
      (node (ref "THRUST7") (pin "P$3") (pinfunction "P$3_P$3") (pintype "bidirectional"))
      (node (ref "THRUST8") (pin "P$1") (pinfunction "P$1_P$1") (pintype "bidirectional"))
      (node (ref "THRUST8") (pin "P$3") (pinfunction "P$3_P$3") (pintype "bidirectional"))
      (node (ref "THRUSTER_CURR_ADC") (pin "11") (pinfunction "COM_11") (pintype "bidirectional"))
      (node (ref "THRUSTER_CURR_ADC") (pin "12") (pinfunction "A0_12") (pintype "bidirectional"))
      (node (ref "THRUSTER_CURR_ADC") (pin "13") (pinfunction "A1_13") (pintype "bidirectional"))
      (node (ref "THRUSTER_CURR_ADC") (pin "9") (pinfunction "GND_9") (pintype "bidirectional"))
      (node (ref "U$1") (pin "P$1") (pinfunction "GND_P$1") (pintype "bidirectional"))
      (node (ref "U$10") (pin "P$1") (pinfunction "A_P$1") (pintype "passive"))
      (node (ref "U$11") (pin "P$5") (pinfunction "GND_P$5") (pintype "bidirectional"))
      (node (ref "U$13") (pin "P$1") (pinfunction "A_P$1") (pintype "passive"))
      (node (ref "U$14") (pin "P$5") (pinfunction "GND_P$5") (pintype "bidirectional"))
      (node (ref "U$16") (pin "P$1") (pinfunction "A_P$1") (pintype "passive"))
      (node (ref "U$17") (pin "P$5") (pinfunction "GND_P$5") (pintype "bidirectional"))
      (node (ref "U$19") (pin "P$5") (pinfunction "GND_P$5") (pintype "bidirectional"))
      (node (ref "U$2") (pin "P$5") (pinfunction "GND_P$5") (pintype "bidirectional"))
      (node (ref "U$22") (pin "P$1") (pinfunction "A_P$1") (pintype "passive"))
      (node (ref "U$23") (pin "P$5") (pinfunction "GND_P$5") (pintype "bidirectional"))
      (node (ref "U$24") (pin "1") (pinfunction "GND_1") (pintype "bidirectional"))
      (node (ref "U$25") (pin "P$1") (pinfunction "GND1_P$1") (pintype "bidirectional"))
      (node (ref "U$25") (pin "P$7") (pinfunction "GND2_P$7") (pintype "bidirectional"))
      (node (ref "U$26") (pin "P$1") (pinfunction "A_P$1") (pintype "passive"))
      (node (ref "U$28") (pin "P$1") (pinfunction "A_P$1") (pintype "passive"))
      (node (ref "U$29") (pin "P$5") (pinfunction "GND_P$5") (pintype "bidirectional"))
      (node (ref "U$30") (pin "P$1") (pinfunction "A_P$1") (pintype "passive"))
      (node (ref "U$31") (pin "P$1") (pinfunction "A_P$1") (pintype "passive"))
      (node (ref "U$32") (pin "P$1") (pinfunction "A_P$1") (pintype "passive"))
      (node (ref "U$33") (pin "P$1") (pinfunction "A_P$1") (pintype "passive"))
      (node (ref "U$34") (pin "P$1") (pinfunction "A_P$1") (pintype "passive"))
      (node (ref "U$35") (pin "P$5") (pinfunction "GND_P$5") (pintype "bidirectional"))
      (node (ref "U$39") (pin "P$5") (pinfunction "GND_P$5") (pintype "bidirectional"))
      (node (ref "U$4") (pin "P$5") (pinfunction "GND_P$5") (pintype "bidirectional"))
      (node (ref "U$41") (pin "P$1") (pinfunction "GND1_P$1") (pintype "bidirectional"))
      (node (ref "U$41") (pin "P$7") (pinfunction "GND2_P$7") (pintype "bidirectional"))
      (node (ref "U$42") (pin "3") (pinfunction "A_3") (pintype "passive"))
      (node (ref "U$43") (pin "3") (pinfunction "A_3") (pintype "passive"))
      (node (ref "U$44") (pin "3") (pinfunction "A_3") (pintype "passive"))
      (node (ref "U$45") (pin "P$1") (pinfunction "A_P$1") (pintype "passive"))
      (node (ref "U$46") (pin "3") (pinfunction "A_3") (pintype "passive"))
      (node (ref "U$47") (pin "3") (pinfunction "A_3") (pintype "passive"))
      (node (ref "U$48") (pin "GND") (pinfunction "GND_GND") (pintype "bidirectional"))
      (node (ref "U$48") (pin "OV") (pinfunction "OV_OV") (pintype "bidirectional"))
      (node (ref "U$51") (pin "GND") (pinfunction "GND_GND") (pintype "bidirectional"))
      (node (ref "U$51") (pin "OV") (pinfunction "OV_OV") (pintype "bidirectional"))
      (node (ref "U$55") (pin "2") (pinfunction "S_2") (pintype "passive"))
      (node (ref "U$56") (pin "P$3") (pinfunction "GND_P$3") (pintype "bidirectional"))
      (node (ref "U$57") (pin "P$1") (pinfunction "GND_P$1") (pintype "bidirectional"))
      (node (ref "U$58") (pin "2") (pinfunction "S_2") (pintype "passive"))
      (node (ref "U$60") (pin "P$3") (pinfunction "A_P$3") (pintype "passive"))
      (node (ref "U$61") (pin "P$3") (pinfunction "A_P$3") (pintype "passive"))
      (node (ref "U$62") (pin "3") (pinfunction "A_3") (pintype "passive"))
      (node (ref "U$63") (pin "P$1") (pinfunction "A_P$1") (pintype "passive"))
      (node (ref "U$64") (pin "P$1") (pinfunction "A_P$1") (pintype "passive"))
      (node (ref "U$66") (pin "P$1") (pinfunction "A_P$1") (pintype "passive"))
      (node (ref "U$67") (pin "P$1") (pinfunction "A_P$1") (pintype "passive"))
      (node (ref "U$68") (pin "P$1") (pinfunction "A_P$1") (pintype "passive"))
      (node (ref "U$7") (pin "5A") (pinfunction "5_5A") (pintype "bidirectional"))
      (node (ref "U$7") (pin "5B") (pinfunction "5_5B") (pintype "bidirectional"))
      (node (ref "U$7") (pin "AA") (pinfunction "A_AA") (pintype "bidirectional"))
      (node (ref "U$7") (pin "AB") (pinfunction "A_AB") (pintype "bidirectional"))
      (node (ref "U$8") (pin "P$5") (pinfunction "GND_P$5") (pintype "bidirectional"))
      (node (ref "U1") (pin "14") (pinfunction "VSS_14") (pintype "bidirectional"))
      (node (ref "U1") (pin "23") (pinfunction "~{OE}_23") (pintype "bidirectional"))
      (node (ref "U1") (pin "25") (pinfunction "EXTCLK_25") (pintype "bidirectional"))
      (node (ref "V-THRUST_CURR_ADC") (pin "P$7") (pinfunction "GND_P$7") (pintype "bidirectional"))
      (node (ref "V-THRUST_LED") (pin "P$2") (pinfunction "C_P$2") (pintype "passive"))
      (node (ref "V-THRUST_OUT") (pin "P$2") (pinfunction "P$2_P$2") (pintype "bidirectional"))
      (node (ref "V-THRUST_VOLTAGE") (pin "P$3") (pinfunction "GND_P$3") (pintype "bidirectional"))
    )
    (net (code "22") (name "Net-(3V3_LED-A)") (class "Default")
      (node (ref "3V3_LED") (pin "P$1") (pinfunction "A_P$1") (pintype "passive"))
      (node (ref "R34") (pin "1") (pinfunction "1_1") (pintype "passive"))
    )
    (net (code "23") (name "Net-(5V_CURR_ADC-VIN)") (class "Default")
      (node (ref "5V_CURR_ADC") (pin "P$4") (pinfunction "VIN_P$4") (pintype "bidirectional"))
      (node (ref "U$2") (pin "P$7") (pinfunction "VIOUT_P$7") (pintype "bidirectional"))
    )
    (net (code "24") (name "Net-(5V_LED-A)") (class "Default")
      (node (ref "5V_LED") (pin "P$1") (pinfunction "A_P$1") (pintype "passive"))
      (node (ref "R31") (pin "1") (pinfunction "1_1") (pintype "passive"))
    )
    (net (code "25") (name "Net-(5V_VOLTAGE-IN+)") (class "Default")
      (node (ref "5V_VOLTAGE") (pin "P$1") (pinfunction "IN+_P$1") (pintype "bidirectional"))
      (node (ref "5V_VOLTAGE") (pin "P$2") (pinfunction "IN-_P$2") (pintype "bidirectional"))
      (node (ref "R35") (pin "2") (pinfunction "2_2") (pintype "passive"))
    )
    (net (code "26") (name "Net-(12V_CURR_ADC-VIN)") (class "Default")
      (node (ref "12V_CURR_ADC") (pin "P$4") (pinfunction "VIN_P$4") (pintype "bidirectional"))
      (node (ref "U$35") (pin "P$7") (pinfunction "VIOUT_P$7") (pintype "bidirectional"))
    )
    (net (code "27") (name "Net-(12V_LED-A)") (class "Default")
      (node (ref "12V_LED") (pin "P$1") (pinfunction "A_P$1") (pintype "passive"))
      (node (ref "R33") (pin "1") (pinfunction "1_1") (pintype "passive"))
    )
    (net (code "28") (name "Net-(12V_VOLTAGE-IN+)") (class "Default")
      (node (ref "12V_VOLTAGE") (pin "P$1") (pinfunction "IN+_P$1") (pintype "bidirectional"))
      (node (ref "12V_VOLTAGE") (pin "P$2") (pinfunction "IN-_P$2") (pintype "bidirectional"))
      (node (ref "R25") (pin "2") (pinfunction "2_2") (pintype "passive"))
    )
    (net (code "29") (name "Net-(C4-Pad1)") (class "Default")
      (node (ref "C4") (pin "1") (pinfunction "1_1") (pintype "passive"))
      (node (ref "U$48") (pin "TMR") (pinfunction "TMR_TMR") (pintype "bidirectional"))
    )
    (net (code "30") (name "Net-(C22-Pad1)") (class "Default")
      (node (ref "C22") (pin "1") (pinfunction "1_1") (pintype "passive"))
      (node (ref "JP3") (pin "2") (pinfunction "2_2") (pintype "passive"))
      (node (ref "U$1") (pin "P$2") (pinfunction "VOUT_P$2") (pintype "bidirectional"))
      (node (ref "U$1") (pin "P$4") (pinfunction "VOUT_P$4") (pintype "bidirectional"))
      (node (ref "U$21") (pin "1") (pinfunction "C_1") (pintype "passive"))
      (node (ref "U$21") (pin "2") (pinfunction "C_2") (pintype "passive"))
    )
    (net (code "31") (name "Net-(C27-Pad1)") (class "Default")
      (node (ref "C27") (pin "1") (pinfunction "1_1") (pintype "passive"))
      (node (ref "U$51") (pin "TMR") (pinfunction "TMR_TMR") (pintype "bidirectional"))
    )
    (net (code "32") (name "Net-(I2C_SHIFT-EN)") (class "Default")
      (node (ref "I2C_SHIFT") (pin "P$7") (pinfunction "VREF2_P$7") (pintype "bidirectional"))
      (node (ref "I2C_SHIFT") (pin "P$8") (pinfunction "EN_P$8") (pintype "bidirectional"))
      (node (ref "R1") (pin "1") (pinfunction "1_1") (pintype "passive"))
    )
    (net (code "33") (name "Net-(LED1-A)") (class "Default")
      (node (ref "LED1") (pin "P$1") (pinfunction "A_P$1") (pintype "passive"))
      (node (ref "R39") (pin "1") (pinfunction "1_1") (pintype "passive"))
    )
    (net (code "34") (name "Net-(LED3-A)") (class "Default")
      (node (ref "LED3") (pin "P$1") (pinfunction "A_P$1") (pintype "passive"))
      (node (ref "R43") (pin "1") (pinfunction "1_1") (pintype "passive"))
    )
    (net (code "35") (name "Net-(LED4-PadC)") (class "Default")
      (node (ref "LED4") (pin "C") (pinfunction "C_C") (pintype "passive"))
      (node (ref "R44") (pin "2") (pinfunction "2_2") (pintype "passive"))
    )
    (net (code "36") (name "Net-(LED5-C)") (class "Default")
      (node (ref "LED5") (pin "P$2") (pinfunction "C_P$2") (pintype "passive"))
      (node (ref "R46") (pin "2") (pinfunction "2_2") (pintype "passive"))
    )
    (net (code "37") (name "Net-(LED6-A)") (class "Default")
      (node (ref "LED6") (pin "P$1") (pinfunction "A_P$1") (pintype "passive"))
      (node (ref "R48") (pin "1") (pinfunction "1_1") (pintype "passive"))
      (node (ref "U$60") (pin "P$1") (pinfunction "C_P$1") (pintype "passive"))
    )
    (net (code "38") (name "Net-(LED7-A)") (class "Default")
      (node (ref "LED7") (pin "P$1") (pinfunction "A_P$1") (pintype "passive"))
      (node (ref "R49") (pin "1") (pinfunction "1_1") (pintype "passive"))
      (node (ref "U$61") (pin "P$1") (pinfunction "C_P$1") (pintype "passive"))
    )
    (net (code "39") (name "Net-(LED8-A)") (class "Default")
      (node (ref "LED8") (pin "P$1") (pinfunction "A_P$1") (pintype "passive"))
      (node (ref "R50") (pin "1") (pinfunction "1_1") (pintype "passive"))
    )
    (net (code "40") (name "Net-(LED9-A)") (class "Default")
      (node (ref "LED9") (pin "P$1") (pinfunction "A_P$1") (pintype "passive"))
      (node (ref "R51") (pin "1") (pinfunction "1_1") (pintype "passive"))
    )
    (net (code "41") (name "Net-(PMOS1-D)") (class "Default")
      (node (ref "PMOS1") (pin "P$2") (pinfunction "D_P$2") (pintype "bidirectional"))
      (node (ref "R39") (pin "2") (pinfunction "2_2") (pintype "passive"))
    )
    (net (code "42") (name "Net-(PMOS1-G)") (class "Default")
      (node (ref "PMOS1") (pin "P$1") (pinfunction "G_P$1") (pintype "bidirectional"))
      (node (ref "R36") (pin "1") (pinfunction "1_1") (pintype "passive"))
      (node (ref "U$51") (pin "FLT") (pinfunction "~{FAULT}_FLT") (pintype "bidirectional"))
    )
    (net (code "43") (name "Net-(PMOS2-D)") (class "Default")
      (node (ref "PMOS2") (pin "P$2") (pinfunction "D_P$2") (pintype "bidirectional"))
      (node (ref "R43") (pin "2") (pinfunction "2_2") (pintype "passive"))
    )
    (net (code "44") (name "Net-(PMOS2-G)") (class "Default")
      (node (ref "PMOS2") (pin "P$1") (pinfunction "G_P$1") (pintype "bidirectional"))
      (node (ref "R41") (pin "1") (pinfunction "1_1") (pintype "passive"))
      (node (ref "U$48") (pin "FLT") (pinfunction "~{FAULT}_FLT") (pintype "bidirectional"))
    )
    (net (code "45") (name "Net-(R2-S)") (class "Default")
      (node (ref "R2") (pin "2") (pinfunction "S_2") (pintype "passive"))
      (node (ref "U$60") (pin "P$2") (pinfunction "REF_P$2") (pintype "bidirectional"))
      (node (ref "U$65") (pin "P$1") (pinfunction "1_P$1") (pintype "bidirectional"))
    )
    (net (code "46") (name "Net-(R3-S)") (class "Default")
      (node (ref "R3") (pin "2") (pinfunction "S_2") (pintype "passive"))
      (node (ref "U$59") (pin "P$1") (pinfunction "1_P$1") (pintype "bidirectional"))
      (node (ref "U$61") (pin "P$2") (pinfunction "REF_P$2") (pintype "bidirectional"))
    )
    (net (code "47") (name "Net-(R5-1)") (class "Default")
      (node (ref "R5") (pin "P$1") (pinfunction "1_P$1") (pintype "passive"))
      (node (ref "U$25") (pin "P$4") (pinfunction "VOADJUST_P$4") (pintype "bidirectional"))
    )
    (net (code "48") (name "Net-(R6-1)") (class "Default")
      (node (ref "R6") (pin "P$1") (pinfunction "1_P$1") (pintype "passive"))
      (node (ref "U$41") (pin "P$4") (pinfunction "VOADJUST_P$4") (pintype "bidirectional"))
    )
    (net (code "49") (name "Net-(R13-Pad2)") (class "Default")
      (node (ref "R13") (pin "2") (pinfunction "2_2") (pintype "passive"))
      (node (ref "R17") (pin "1") (pinfunction "1_1") (pintype "passive"))
      (node (ref "U$51") (pin "UV") (pinfunction "UV_UV") (pintype "bidirectional"))
    )
    (net (code "50") (name "Net-(R14-Pad1)") (class "Default")
      (node (ref "R14") (pin "1") (pinfunction "1_1") (pintype "passive"))
      (node (ref "R20") (pin "2") (pinfunction "2_2") (pintype "passive"))
      (node (ref "U$51") (pin "FB") (pinfunction "FB_FB") (pintype "bidirectional"))
    )
    (net (code "51") (name "Net-(R14-Pad2)") (class "Default")
      (node (ref "R14") (pin "2") (pinfunction "2_2") (pintype "passive"))
      (node (ref "R19") (pin "1") (pinfunction "1_1") (pintype "passive"))
    )
    (net (code "52") (name "Net-(R16-Pad1)") (class "Default")
      (node (ref "R16") (pin "1") (pinfunction "1_1") (pintype "passive"))
      (node (ref "U$51") (pin "HGATE") (pinfunction "HGATE_HGATE") (pintype "bidirectional"))
    )
    (net (code "53") (name "Net-(R23-Pad1)") (class "Default")
      (node (ref "R23") (pin "1") (pinfunction "1_1") (pintype "passive"))
      (node (ref "R24") (pin "2") (pinfunction "2_2") (pintype "passive"))
      (node (ref "U$48") (pin "FB") (pinfunction "FB_FB") (pintype "bidirectional"))
    )
    (net (code "54") (name "Net-(R23-Pad2)") (class "Default")
      (node (ref "R23") (pin "2") (pinfunction "2_2") (pintype "passive"))
      (node (ref "R28") (pin "1") (pinfunction "1_1") (pintype "passive"))
    )
    (net (code "55") (name "Net-(R26-Pad1)") (class "Default")
      (node (ref "R26") (pin "1") (pinfunction "1_1") (pintype "passive"))
      (node (ref "U$48") (pin "HGATE") (pinfunction "HGATE_HGATE") (pintype "bidirectional"))
    )
    (net (code "56") (name "Net-(R27-Pad1)") (class "Default")
      (node (ref "R27") (pin "1") (pinfunction "1_1") (pintype "passive"))
      (node (ref "R9") (pin "2") (pinfunction "2_2") (pintype "passive"))
      (node (ref "U$48") (pin "UV") (pinfunction "UV_UV") (pintype "bidirectional"))
    )
    (net (code "57") (name "Net-(U$2-FILTER)") (class "Default")
      (node (ref "C3") (pin "1") (pinfunction "1_1") (pintype "passive"))
      (node (ref "U$2") (pin "P$6") (pinfunction "FILTER_P$6") (pintype "bidirectional"))
    )
    (net (code "58") (name "Net-(U$2-IP--PadP$3)") (class "Default")
      (node (ref "U$2") (pin "P$3") (pinfunction "IP-_P$3") (pintype "bidirectional"))
      (node (ref "U$2") (pin "P$4") (pinfunction "IP-_P$4") (pintype "bidirectional"))
      (node (ref "U$20") (pin "P$1") (pinfunction "P$1_P$1") (pintype "bidirectional"))
    )
    (net (code "59") (name "Net-(U$4-FILTER)") (class "Default")
      (node (ref "C6") (pin "1") (pinfunction "1_1") (pintype "passive"))
      (node (ref "U$4") (pin "P$6") (pinfunction "FILTER_P$6") (pintype "bidirectional"))
    )
    (net (code "60") (name "Net-(U$4-IP--PadP$3)") (class "Default")
      (node (ref "U$4") (pin "P$3") (pinfunction "IP-_P$3") (pintype "bidirectional"))
      (node (ref "U$4") (pin "P$4") (pinfunction "IP-_P$4") (pintype "bidirectional"))
      (node (ref "U$6") (pin "P$1") (pinfunction "P$1_P$1") (pintype "bidirectional"))
    )
    (net (code "61") (name "Net-(U$8-FILTER)") (class "Default")
      (node (ref "C9") (pin "1") (pinfunction "1_1") (pintype "passive"))
      (node (ref "U$8") (pin "P$6") (pinfunction "FILTER_P$6") (pintype "bidirectional"))
    )
    (net (code "62") (name "Net-(U$8-IP--PadP$3)") (class "Default")
      (node (ref "U$8") (pin "P$3") (pinfunction "IP-_P$3") (pintype "bidirectional"))
      (node (ref "U$8") (pin "P$4") (pinfunction "IP-_P$4") (pintype "bidirectional"))
      (node (ref "U$9") (pin "P$1") (pinfunction "P$1_P$1") (pintype "bidirectional"))
    )
    (net (code "63") (name "Net-(U$11-FILTER)") (class "Default")
      (node (ref "C12") (pin "1") (pinfunction "1_1") (pintype "passive"))
      (node (ref "U$11") (pin "P$6") (pinfunction "FILTER_P$6") (pintype "bidirectional"))
    )
    (net (code "64") (name "Net-(U$11-IP--PadP$3)") (class "Default")
      (node (ref "U$11") (pin "P$3") (pinfunction "IP-_P$3") (pintype "bidirectional"))
      (node (ref "U$11") (pin "P$4") (pinfunction "IP-_P$4") (pintype "bidirectional"))
      (node (ref "U$12") (pin "P$1") (pinfunction "P$1_P$1") (pintype "bidirectional"))
    )
    (net (code "65") (name "Net-(U$14-FILTER)") (class "Default")
      (node (ref "C15") (pin "1") (pinfunction "1_1") (pintype "passive"))
      (node (ref "U$14") (pin "P$6") (pinfunction "FILTER_P$6") (pintype "bidirectional"))
    )
    (net (code "66") (name "Net-(U$14-IP--PadP$3)") (class "Default")
      (node (ref "U$14") (pin "P$3") (pinfunction "IP-_P$3") (pintype "bidirectional"))
      (node (ref "U$14") (pin "P$4") (pinfunction "IP-_P$4") (pintype "bidirectional"))
      (node (ref "U$15") (pin "P$1") (pinfunction "P$1_P$1") (pintype "bidirectional"))
    )
    (net (code "67") (name "Net-(U$17-FILTER)") (class "Default")
      (node (ref "C18") (pin "1") (pinfunction "1_1") (pintype "passive"))
      (node (ref "U$17") (pin "P$6") (pinfunction "FILTER_P$6") (pintype "bidirectional"))
    )
    (net (code "68") (name "Net-(U$17-IP--PadP$3)") (class "Default")
      (node (ref "U$17") (pin "P$3") (pinfunction "IP-_P$3") (pintype "bidirectional"))
      (node (ref "U$17") (pin "P$4") (pinfunction "IP-_P$4") (pintype "bidirectional"))
      (node (ref "U$18") (pin "P$1") (pinfunction "P$1_P$1") (pintype "bidirectional"))
    )
    (net (code "69") (name "Net-(U$19-FILTER)") (class "Default")
      (node (ref "C20") (pin "1") (pinfunction "1_1") (pintype "passive"))
      (node (ref "U$19") (pin "P$6") (pinfunction "FILTER_P$6") (pintype "bidirectional"))
    )
    (net (code "70") (name "Net-(U$19-IP--PadP$3)") (class "Default")
      (node (ref "U$19") (pin "P$3") (pinfunction "IP-_P$3") (pintype "bidirectional"))
      (node (ref "U$19") (pin "P$4") (pinfunction "IP-_P$4") (pintype "bidirectional"))
      (node (ref "U$5") (pin "P$1") (pinfunction "P$1_P$1") (pintype "bidirectional"))
      (node (ref "U$5") (pin "P$2") (pinfunction "P$1_P$2") (pintype "bidirectional"))
    )
    (net (code "71") (name "Net-(U$19-VIOUT)") (class "Default")
      (node (ref "U$19") (pin "P$7") (pinfunction "VIOUT_P$7") (pintype "bidirectional"))
      (node (ref "V-THRUST_CURR_ADC") (pin "P$4") (pinfunction "VIN_P$4") (pintype "bidirectional"))
    )
    (net (code "72") (name "Net-(U$21-A)") (class "Default")
      (node (ref "C23") (pin "1") (pinfunction "1_1") (pintype "passive"))
      (node (ref "JP3") (pin "1") (pinfunction "1_1") (pintype "passive"))
      (node (ref "R4") (pin "2") (pinfunction "2_2") (pintype "passive"))
      (node (ref "U$21") (pin "3") (pinfunction "A_3") (pintype "passive"))
      (node (ref "U$24") (pin "2") (pinfunction "IN_2") (pintype "bidirectional"))
    )
    (net (code "73") (name "Net-(U$23-FILTER)") (class "Default")
      (node (ref "C29") (pin "1") (pinfunction "1_1") (pintype "passive"))
      (node (ref "U$23") (pin "P$6") (pinfunction "FILTER_P$6") (pintype "bidirectional"))
    )
    (net (code "74") (name "Net-(U$23-IP--PadP$3)") (class "Default")
      (node (ref "U$23") (pin "P$3") (pinfunction "IP-_P$3") (pintype "bidirectional"))
      (node (ref "U$23") (pin "P$4") (pinfunction "IP-_P$4") (pintype "bidirectional"))
      (node (ref "U$27") (pin "P$1") (pinfunction "P$1_P$1") (pintype "bidirectional"))
    )
    (net (code "75") (name "Net-(U$25-~{INHIBIT})") (class "Default")
      (node (ref "JP1") (pin "2") (pinfunction "2_2") (pintype "passive"))
      (node (ref "U$25") (pin "P$3") (pinfunction "~{INHIBIT}_P$3") (pintype "bidirectional"))
    )
    (net (code "76") (name "Net-(U$29-FILTER)") (class "Default")
      (node (ref "C37") (pin "1") (pinfunction "1_1") (pintype "passive"))
      (node (ref "U$29") (pin "P$6") (pinfunction "FILTER_P$6") (pintype "bidirectional"))
    )
    (net (code "77") (name "Net-(U$29-IP--PadP$3)") (class "Default")
      (node (ref "U$29") (pin "P$3") (pinfunction "IP-_P$3") (pintype "bidirectional"))
      (node (ref "U$29") (pin "P$4") (pinfunction "IP-_P$4") (pintype "bidirectional"))
      (node (ref "U$37") (pin "P$1") (pinfunction "P$1_P$1") (pintype "bidirectional"))
    )
    (net (code "78") (name "Net-(U$35-FILTER)") (class "Default")
      (node (ref "C31") (pin "1") (pinfunction "1_1") (pintype "passive"))
      (node (ref "U$35") (pin "P$6") (pinfunction "FILTER_P$6") (pintype "bidirectional"))
    )
    (net (code "79") (name "Net-(U$35-IP--PadP$3)") (class "Default")
      (node (ref "U$35") (pin "P$3") (pinfunction "IP-_P$3") (pintype "bidirectional"))
      (node (ref "U$35") (pin "P$4") (pinfunction "IP-_P$4") (pintype "bidirectional"))
      (node (ref "U$36") (pin "P$1") (pinfunction "P$1_P$1") (pintype "bidirectional"))
    )
    (net (code "80") (name "Net-(U$39-FILTER)") (class "Default")
      (node (ref "C57") (pin "1") (pinfunction "1_1") (pintype "passive"))
      (node (ref "U$39") (pin "P$6") (pinfunction "FILTER_P$6") (pintype "bidirectional"))
    )
    (net (code "81") (name "Net-(U$39-IP--PadP$3)") (class "Default")
      (node (ref "U$39") (pin "P$3") (pinfunction "IP-_P$3") (pintype "bidirectional"))
      (node (ref "U$39") (pin "P$4") (pinfunction "IP-_P$4") (pintype "bidirectional"))
      (node (ref "U$40") (pin "P$1") (pinfunction "P$1_P$1") (pintype "bidirectional"))
    )
    (net (code "82") (name "Net-(U$41-~{INHIBIT})") (class "Default")
      (node (ref "JP2") (pin "2") (pinfunction "2_2") (pintype "passive"))
      (node (ref "U$41") (pin "P$3") (pinfunction "~{INHIBIT}_P$3") (pintype "bidirectional"))
    )
    (net (code "83") (name "Net-(U$45-C)") (class "Default")
      (node (ref "C30") (pin "1") (pinfunction "1_1") (pintype "passive"))
      (node (ref "JP4") (pin "2") (pinfunction "2_2") (pintype "passive"))
      (node (ref "U$24") (pin "6") (pinfunction "OUT_6") (pintype "bidirectional"))
      (node (ref "U$24") (pin "7") (pinfunction "OUT_7") (pintype "bidirectional"))
      (node (ref "U$24") (pin "8") (pinfunction "OUT_8") (pintype "bidirectional"))
      (node (ref "U$45") (pin "P$2") (pinfunction "C_P$2") (pintype "passive"))
      (node (ref "U$7") (pin "BA") (pinfunction "B_BA") (pintype "bidirectional"))
      (node (ref "U$7") (pin "BB") (pinfunction "B_BB") (pintype "bidirectional"))
    )
    (net (code "84") (name "Net-(U$48-~{SHDN})") (class "Default")
      (node (ref "SHDN_JMP") (pin "2") (pinfunction "2_2") (pintype "passive"))
      (node (ref "U$48") (pin "SHDN") (pinfunction "~{SHDN}_SHDN") (pintype "bidirectional"))
      (node (ref "U$51") (pin "SHDN") (pinfunction "~{SHDN}_SHDN") (pintype "bidirectional"))
      (node (ref "U$56") (pin "P$4") (pinfunction "OUT_P$4") (pintype "bidirectional"))
    )
    (net (code "85") (name "Net-(U$49-G)") (class "Default")
      (node (ref "R26") (pin "2") (pinfunction "2_2") (pintype "passive"))
      (node (ref "U$49") (pin "1") (pinfunction "G_1") (pintype "bidirectional"))
    )
    (net (code "86") (name "Net-(U$49-S)") (class "Default")
      (node (ref "U$48") (pin "SOURCE") (pinfunction "SOURCE_SOURCE") (pintype "bidirectional"))
      (node (ref "U$49") (pin "3") (pinfunction "S_3") (pintype "bidirectional"))
      (node (ref "U$50") (pin "3") (pinfunction "S_3") (pintype "bidirectional"))
    )
    (net (code "87") (name "Net-(U$50-D)") (class "Default")
      (node (ref "R12") (pin "1") (pinfunction "1_1") (pintype "passive"))
      (node (ref "U$48") (pin "SENSE") (pinfunction "SENSE_SENSE") (pintype "bidirectional"))
      (node (ref "U$50") (pin "TAB") (pinfunction "D_TAB") (pintype "bidirectional"))
    )
    (net (code "88") (name "Net-(U$50-G)") (class "Default")
      (node (ref "U$48") (pin "DGATE") (pinfunction "DGATE_DGATE") (pintype "bidirectional"))
      (node (ref "U$50") (pin "1") (pinfunction "G_1") (pintype "bidirectional"))
    )
    (net (code "89") (name "Net-(U$52-G)") (class "Default")
      (node (ref "R16") (pin "2") (pinfunction "2_2") (pintype "passive"))
      (node (ref "U$52") (pin "1") (pinfunction "G_1") (pintype "bidirectional"))
    )
    (net (code "90") (name "Net-(U$52-S)") (class "Default")
      (node (ref "U$51") (pin "SOURCE") (pinfunction "SOURCE_SOURCE") (pintype "bidirectional"))
      (node (ref "U$52") (pin "3") (pinfunction "S_3") (pintype "bidirectional"))
      (node (ref "U$53") (pin "3") (pinfunction "S_3") (pintype "bidirectional"))
    )
    (net (code "91") (name "Net-(U$53-D)") (class "Default")
      (node (ref "R15") (pin "1") (pinfunction "1_1") (pintype "passive"))
      (node (ref "U$51") (pin "SENSE") (pinfunction "SENSE_SENSE") (pintype "bidirectional"))
      (node (ref "U$53") (pin "TAB") (pinfunction "D_TAB") (pintype "bidirectional"))
    )
    (net (code "92") (name "Net-(U$53-G)") (class "Default")
      (node (ref "U$51") (pin "DGATE") (pinfunction "DGATE_DGATE") (pintype "bidirectional"))
      (node (ref "U$53") (pin "1") (pinfunction "G_1") (pintype "bidirectional"))
    )
    (net (code "93") (name "Net-(U$55-D)") (class "Default")
      (node (ref "R44") (pin "1") (pinfunction "1_1") (pintype "passive"))
      (node (ref "U$55") (pin "3") (pinfunction "D_3") (pintype "bidirectional"))
    )
    (net (code "94") (name "Net-(U$55-G)") (class "Default")
      (node (ref "R45") (pin "1") (pinfunction "1_1") (pintype "passive"))
      (node (ref "U$48") (pin "ENOUT") (pinfunction "ENOUT_ENOUT") (pintype "bidirectional"))
      (node (ref "U$55") (pin "1") (pinfunction "G_1") (pintype "passive"))
    )
    (net (code "95") (name "Net-(U$56-IN)") (class "Default")
      (node (ref "C60") (pin "1") (pinfunction "1_1") (pintype "passive"))
      (node (ref "R22") (pin "2") (pinfunction "2_2") (pintype "passive"))
      (node (ref "U$56") (pin "P$2") (pinfunction "IN_P$2") (pintype "bidirectional"))
    )
    (net (code "96") (name "Net-(U$58-D)") (class "Default")
      (node (ref "R46") (pin "1") (pinfunction "1_1") (pintype "passive"))
      (node (ref "U$58") (pin "3") (pinfunction "D_3") (pintype "bidirectional"))
    )
    (net (code "97") (name "Net-(U$58-G)") (class "Default")
      (node (ref "R47") (pin "1") (pinfunction "1_1") (pintype "passive"))
      (node (ref "U$51") (pin "ENOUT") (pinfunction "ENOUT_ENOUT") (pintype "bidirectional"))
      (node (ref "U$58") (pin "1") (pinfunction "G_1") (pintype "passive"))
    )
    (net (code "98") (name "Net-(V-THRUST_LED-A)") (class "Default")
      (node (ref "R32") (pin "1") (pinfunction "1_1") (pintype "passive"))
      (node (ref "V-THRUST_LED") (pin "P$1") (pinfunction "A_P$1") (pintype "passive"))
    )
    (net (code "99") (name "Net-(V-THRUST_VOLTAGE-IN+)") (class "Default")
      (node (ref "R30") (pin "2") (pinfunction "2_2") (pintype "passive"))
      (node (ref "V-THRUST_VOLTAGE") (pin "P$1") (pinfunction "IN+_P$1") (pintype "bidirectional"))
      (node (ref "V-THRUST_VOLTAGE") (pin "P$2") (pinfunction "IN-_P$2") (pintype "bidirectional"))
    )
    (net (code "100") (name "SCL") (class "Default")
      (node (ref "12V_CURR_ADC") (pin "P$1") (pinfunction "SCL_P$1") (pintype "bidirectional"))
      (node (ref "12V_VOLTAGE") (pin "P$5") (pinfunction "SCL_P$5") (pintype "bidirectional"))
      (node (ref "5V_CURR_ADC") (pin "P$1") (pinfunction "SCL_P$1") (pintype "bidirectional"))
      (node (ref "5V_VOLTAGE") (pin "P$5") (pinfunction "SCL_P$5") (pintype "bidirectional"))
      (node (ref "I2C") (pin "2") (pinfunction "2_2") (pintype "passive"))
      (node (ref "R8") (pin "1") (pinfunction "1_1") (pintype "passive"))
      (node (ref "THRUSTER_CURR_ADC") (pin "14") (pinfunction "SCL_14") (pintype "bidirectional"))
      (node (ref "U$71") (pin "P$1") (pinfunction "1_P$1") (pintype "bidirectional"))
      (node (ref "U1") (pin "26") (pinfunction "SCL_26") (pintype "bidirectional"))
      (node (ref "V-THRUST_CURR_ADC") (pin "P$1") (pinfunction "SCL_P$1") (pintype "bidirectional"))
      (node (ref "V-THRUST_VOLTAGE") (pin "P$5") (pinfunction "SCL_P$5") (pintype "bidirectional"))
    )
    (net (code "101") (name "SCL-3V3") (class "Default")
      (node (ref "BME280") (pin "P$4") (pinfunction "SCK/SCL_P$4") (pintype "bidirectional"))
      (node (ref "DEPTH_SENS") (pin "P$1") (pinfunction "P$1_P$1") (pintype "bidirectional"))
      (node (ref "I2C_SHIFT") (pin "P$3") (pinfunction "SCL1_P$3") (pintype "bidirectional"))
      (node (ref "R11") (pin "1") (pinfunction "1_1") (pintype "passive"))
    )
    (net (code "102") (name "SDA") (class "Default")
      (node (ref "12V_CURR_ADC") (pin "P$8") (pinfunction "SDA_P$8") (pintype "bidirectional"))
      (node (ref "12V_VOLTAGE") (pin "P$6") (pinfunction "SDA_P$6") (pintype "bidirectional"))
      (node (ref "5V_CURR_ADC") (pin "P$8") (pinfunction "SDA_P$8") (pintype "bidirectional"))
      (node (ref "5V_VOLTAGE") (pin "P$6") (pinfunction "SDA_P$6") (pintype "bidirectional"))
      (node (ref "I2C") (pin "1") (pinfunction "1_1") (pintype "passive"))
      (node (ref "R7") (pin "1") (pinfunction "1_1") (pintype "passive"))
      (node (ref "THRUSTER_CURR_ADC") (pin "15") (pinfunction "SDA_15") (pintype "bidirectional"))
      (node (ref "U$72") (pin "P$1") (pinfunction "1_P$1") (pintype "bidirectional"))
      (node (ref "U1") (pin "27") (pinfunction "SDA_27") (pintype "bidirectional"))
      (node (ref "V-THRUST_CURR_ADC") (pin "P$8") (pinfunction "SDA_P$8") (pintype "bidirectional"))
      (node (ref "V-THRUST_VOLTAGE") (pin "P$6") (pinfunction "SDA_P$6") (pintype "bidirectional"))
    )
    (net (code "103") (name "SDA-3V3") (class "Default")
      (node (ref "BME280") (pin "P$3") (pinfunction "SDI/SDA_P$3") (pintype "bidirectional"))
      (node (ref "DEPTH_SENS") (pin "P$2") (pinfunction "P$2_P$2") (pintype "bidirectional"))
      (node (ref "I2C_SHIFT") (pin "P$4") (pinfunction "SDA1_P$4") (pintype "bidirectional"))
      (node (ref "R10") (pin "1") (pinfunction "1_1") (pintype "passive"))
    )
    (net (code "104") (name "T1_CURR") (class "Default")
      (node (ref "THRUSTER_CURR_ADC") (pin "1") (pinfunction "CH0_1") (pintype "bidirectional"))
      (node (ref "U$4") (pin "P$7") (pinfunction "VIOUT_P$7") (pintype "bidirectional"))
    )
    (net (code "105") (name "T3_CURR") (class "Default")
      (node (ref "THRUSTER_CURR_ADC") (pin "3") (pinfunction "CH2_3") (pintype "bidirectional"))
      (node (ref "U$11") (pin "P$7") (pinfunction "VIOUT_P$7") (pintype "bidirectional"))
    )
    (net (code "106") (name "T4_CURR") (class "Default")
      (node (ref "THRUSTER_CURR_ADC") (pin "4") (pinfunction "CH3_4") (pintype "bidirectional"))
      (node (ref "U$14") (pin "P$7") (pinfunction "VIOUT_P$7") (pintype "bidirectional"))
    )
    (net (code "107") (name "T5_CURR") (class "Default")
      (node (ref "THRUSTER_CURR_ADC") (pin "5") (pinfunction "CH4_5") (pintype "bidirectional"))
      (node (ref "U$17") (pin "P$7") (pinfunction "VIOUT_P$7") (pintype "bidirectional"))
    )
    (net (code "108") (name "T6_CURR") (class "Default")
      (node (ref "THRUSTER_CURR_ADC") (pin "6") (pinfunction "CH5_6") (pintype "bidirectional"))
      (node (ref "U$23") (pin "P$7") (pinfunction "VIOUT_P$7") (pintype "bidirectional"))
    )
    (net (code "109") (name "T7_CURR") (class "Default")
      (node (ref "THRUSTER_CURR_ADC") (pin "7") (pinfunction "CH6_7") (pintype "bidirectional"))
      (node (ref "U$29") (pin "P$7") (pinfunction "VIOUT_P$7") (pintype "bidirectional"))
    )
    (net (code "110") (name "T8_CURR") (class "Default")
      (node (ref "THRUSTER_CURR_ADC") (pin "8") (pinfunction "CH7_8") (pintype "bidirectional"))
      (node (ref "U$39") (pin "P$7") (pinfunction "VIOUT_P$7") (pintype "bidirectional"))
    )
    (net (code "111") (name "VIN") (class "Default")
      (node (ref "C17") (pin "1") (pinfunction "1_1") (pintype "passive"))
      (node (ref "C28") (pin "1") (pinfunction "1_1") (pintype "passive"))
      (node (ref "C65") (pin "1") (pinfunction "1_1") (pintype "passive"))
      (node (ref "CIN1") (pin "1") (pinfunction "1_1") (pintype "passive"))
      (node (ref "CIN2") (pin "1") (pinfunction "1_1") (pintype "passive"))
      (node (ref "CIN3") (pin "1") (pinfunction "1_1") (pintype "passive"))
      (node (ref "CIN4") (pin "1") (pinfunction "1_1") (pintype "passive"))
      (node (ref "R12") (pin "2") (pinfunction "2_2") (pintype "passive"))
      (node (ref "R15") (pin "2") (pinfunction "2_2") (pintype "passive"))
      (node (ref "R19") (pin "2") (pinfunction "2_2") (pintype "passive"))
      (node (ref "R28") (pin "2") (pinfunction "2_2") (pintype "passive"))
      (node (ref "SHORE_IN") (pin "P$1") (pinfunction "P$1_P$1") (pintype "bidirectional"))
      (node (ref "U$1") (pin "P$3") (pinfunction "VIN_P$3") (pintype "bidirectional"))
      (node (ref "U$25") (pin "P$2") (pinfunction "VI_P$2") (pintype "bidirectional"))
      (node (ref "U$41") (pin "P$2") (pinfunction "VI_P$2") (pintype "bidirectional"))
      (node (ref "U$48") (pin "OUT") (pinfunction "OUT_OUT") (pintype "bidirectional"))
      (node (ref "U$51") (pin "OUT") (pinfunction "OUT_OUT") (pintype "bidirectional"))
      (node (ref "U$66") (pin "P$2") (pinfunction "C_P$2") (pintype "passive"))
      (node (ref "U$7") (pin "2A") (pinfunction "2_2A") (pintype "bidirectional"))
      (node (ref "U$7") (pin "2B") (pinfunction "2_2B") (pintype "bidirectional"))
      (node (ref "U$73") (pin "P$1") (pinfunction "1_P$1") (pintype "bidirectional"))
    )
    (net (code "112") (name "V_RELAY") (class "Default")
      (node (ref "U$19") (pin "P$1") (pinfunction "IP+_P$1") (pintype "bidirectional"))
      (node (ref "U$19") (pin "P$2") (pinfunction "IP+_P$2") (pintype "bidirectional"))
      (node (ref "U$7") (pin "7A") (pinfunction "7_7A") (pintype "bidirectional"))
      (node (ref "U$7") (pin "7B") (pinfunction "7_7B") (pintype "bidirectional"))
    )
    (net (code "113") (name "V_THRUST") (class "Default")
      (node (ref "C21") (pin "1") (pinfunction "1_1") (pintype "passive"))
      (node (ref "C43") (pin "+") (pinfunction "+_+") (pintype "passive"))
      (node (ref "C44") (pin "+") (pinfunction "+_+") (pintype "passive"))
      (node (ref "C46") (pin "1") (pinfunction "1_1") (pintype "passive"))
      (node (ref "C47") (pin "1") (pinfunction "1_1") (pintype "passive"))
      (node (ref "CAMERA1") (pin "P$1") (pinfunction "P$1_P$1") (pintype "bidirectional"))
      (node (ref "CAMERA2") (pin "P$1") (pinfunction "P$1_P$1") (pintype "bidirectional"))
      (node (ref "R30") (pin "1") (pinfunction "1_1") (pintype "passive"))
      (node (ref "R32") (pin "2") (pinfunction "2_2") (pintype "passive"))
      (node (ref "U$11") (pin "P$1") (pinfunction "IP+_P$1") (pintype "bidirectional"))
      (node (ref "U$11") (pin "P$2") (pinfunction "IP+_P$2") (pintype "bidirectional"))
      (node (ref "U$14") (pin "P$1") (pinfunction "IP+_P$1") (pintype "bidirectional"))
      (node (ref "U$14") (pin "P$2") (pinfunction "IP+_P$2") (pintype "bidirectional"))
      (node (ref "U$17") (pin "P$1") (pinfunction "IP+_P$1") (pintype "bidirectional"))
      (node (ref "U$17") (pin "P$2") (pinfunction "IP+_P$2") (pintype "bidirectional"))
      (node (ref "U$23") (pin "P$1") (pinfunction "IP+_P$1") (pintype "bidirectional"))
      (node (ref "U$23") (pin "P$2") (pinfunction "IP+_P$2") (pintype "bidirectional"))
      (node (ref "U$29") (pin "P$1") (pinfunction "IP+_P$1") (pintype "bidirectional"))
      (node (ref "U$29") (pin "P$2") (pinfunction "IP+_P$2") (pintype "bidirectional"))
      (node (ref "U$32") (pin "P$2") (pinfunction "C_P$2") (pintype "passive"))
      (node (ref "U$33") (pin "P$2") (pinfunction "C_P$2") (pintype "passive"))
      (node (ref "U$34") (pin "P$2") (pinfunction "C_P$2") (pintype "passive"))
      (node (ref "U$39") (pin "P$1") (pinfunction "IP+_P$1") (pintype "bidirectional"))
      (node (ref "U$39") (pin "P$2") (pinfunction "IP+_P$2") (pintype "bidirectional"))
      (node (ref "U$4") (pin "P$1") (pinfunction "IP+_P$1") (pintype "bidirectional"))
      (node (ref "U$4") (pin "P$2") (pinfunction "IP+_P$2") (pintype "bidirectional"))
      (node (ref "U$5") (pin "P$3") (pinfunction "P$2_P$3") (pintype "bidirectional"))
      (node (ref "U$5") (pin "P$4") (pinfunction "P$2_P$4") (pintype "bidirectional"))
      (node (ref "U$54") (pin "P$1") (pinfunction "1_P$1") (pintype "bidirectional"))
      (node (ref "U$8") (pin "P$1") (pinfunction "IP+_P$1") (pintype "bidirectional"))
      (node (ref "U$8") (pin "P$2") (pinfunction "IP+_P$2") (pintype "bidirectional"))
      (node (ref "V-THRUST_OUT") (pin "P$1") (pinfunction "P$1_P$1") (pintype "bidirectional"))
    )
    (net (code "114") (name "V_THRUST1") (class "Default")
      (node (ref "C10") (pin "1") (pinfunction "1_1") (pintype "passive"))
      (node (ref "C76") (pin "1") (pinfunction "1_1") (pintype "passive"))
      (node (ref "THRUST1") (pin "P$4") (pinfunction "P$4_P$4") (pintype "bidirectional"))
      (node (ref "U$31") (pin "P$2") (pinfunction "C_P$2") (pintype "passive"))
      (node (ref "U$6") (pin "P$2") (pinfunction "P$2_P$2") (pintype "bidirectional"))
    )
    (net (code "115") (name "V_THRUST2") (class "Default")
      (node (ref "C74") (pin "1") (pinfunction "1_1") (pintype "passive"))
      (node (ref "C75") (pin "1") (pinfunction "1_1") (pintype "passive"))
      (node (ref "THRUST2") (pin "P$4") (pinfunction "P$4_P$4") (pintype "bidirectional"))
      (node (ref "U$30") (pin "P$2") (pinfunction "C_P$2") (pintype "passive"))
      (node (ref "U$9") (pin "P$2") (pinfunction "P$2_P$2") (pintype "bidirectional"))
    )
    (net (code "116") (name "V_THRUST3") (class "Default")
      (node (ref "C107") (pin "1") (pinfunction "1_1") (pintype "passive"))
      (node (ref "C108") (pin "1") (pinfunction "1_1") (pintype "passive"))
      (node (ref "THRUST3") (pin "P$4") (pinfunction "P$4_P$4") (pintype "bidirectional"))
      (node (ref "U$12") (pin "P$2") (pinfunction "P$2_P$2") (pintype "bidirectional"))
      (node (ref "U$26") (pin "P$2") (pinfunction "C_P$2") (pintype "passive"))
    )
    (net (code "117") (name "V_THRUST4") (class "Default")
      (node (ref "C80") (pin "1") (pinfunction "1_1") (pintype "passive"))
      (node (ref "C88") (pin "1") (pinfunction "1_1") (pintype "passive"))
      (node (ref "THRUST4") (pin "P$4") (pinfunction "P$4_P$4") (pintype "bidirectional"))
      (node (ref "U$15") (pin "P$2") (pinfunction "P$2_P$2") (pintype "bidirectional"))
      (node (ref "U$28") (pin "P$2") (pinfunction "C_P$2") (pintype "passive"))
    )
    (net (code "118") (name "V_THRUST5") (class "Default")
      (node (ref "C110") (pin "1") (pinfunction "1_1") (pintype "passive"))
      (node (ref "C111") (pin "1") (pinfunction "1_1") (pintype "passive"))
      (node (ref "THRUST5") (pin "P$4") (pinfunction "P$4_P$4") (pintype "bidirectional"))
      (node (ref "U$18") (pin "P$2") (pinfunction "P$2_P$2") (pintype "bidirectional"))
      (node (ref "U$22") (pin "P$2") (pinfunction "C_P$2") (pintype "passive"))
    )
    (net (code "119") (name "V_THRUST6") (class "Default")
      (node (ref "C101") (pin "1") (pinfunction "1_1") (pintype "passive"))
      (node (ref "C102") (pin "1") (pinfunction "1_1") (pintype "passive"))
      (node (ref "THRUST6") (pin "P$4") (pinfunction "P$4_P$4") (pintype "bidirectional"))
      (node (ref "U$13") (pin "P$2") (pinfunction "C_P$2") (pintype "passive"))
      (node (ref "U$27") (pin "P$2") (pinfunction "P$2_P$2") (pintype "bidirectional"))
    )
    (net (code "120") (name "V_THRUST7") (class "Default")
      (node (ref "C113") (pin "1") (pinfunction "1_1") (pintype "passive"))
      (node (ref "C114") (pin "1") (pinfunction "1_1") (pintype "passive"))
      (node (ref "THRUST7") (pin "P$4") (pinfunction "P$4_P$4") (pintype "bidirectional"))
      (node (ref "U$16") (pin "P$2") (pinfunction "C_P$2") (pintype "passive"))
      (node (ref "U$37") (pin "P$2") (pinfunction "P$2_P$2") (pintype "bidirectional"))
    )
    (net (code "121") (name "V_THRUST8") (class "Default")
      (node (ref "C104") (pin "1") (pinfunction "1_1") (pintype "passive"))
      (node (ref "C105") (pin "1") (pinfunction "1_1") (pintype "passive"))
      (node (ref "THRUST8") (pin "P$4") (pinfunction "P$4_P$4") (pintype "bidirectional"))
      (node (ref "U$10") (pin "P$2") (pinfunction "C_P$2") (pintype "passive"))
      (node (ref "U$40") (pin "P$2") (pinfunction "P$2_P$2") (pintype "bidirectional"))
    )
    (net (code "122") (name "unconnected-(5V_CURR_ADC-ALERT-PadP$2)") (class "Default")
      (node (ref "5V_CURR_ADC") (pin "P$2") (pinfunction "ALERT_P$2") (pintype "bidirectional"))
    )
    (net (code "123") (name "unconnected-(12V_CURR_ADC-ALERT-PadP$2)") (class "Default")
      (node (ref "12V_CURR_ADC") (pin "P$2") (pinfunction "ALERT_P$2") (pintype "bidirectional"))
    )
    (net (code "124") (name "unconnected-(U$24-DEN-Pad3)") (class "Default")
      (node (ref "U$24") (pin "3") (pinfunction "DEN_3") (pintype "bidirectional"))
    )
    (net (code "125") (name "unconnected-(U$24-IS-Pad4)") (class "Default")
      (node (ref "U$24") (pin "4") (pinfunction "IS_4") (pintype "bidirectional"))
    )
    (net (code "126") (name "unconnected-(U1-CH8-Pad15)") (class "Default")
      (node (ref "U1") (pin "15") (pinfunction "CH8_15") (pintype "bidirectional"))
    )
    (net (code "127") (name "unconnected-(U1-CH9-Pad16)") (class "Default")
      (node (ref "U1") (pin "16") (pinfunction "CH9_16") (pintype "bidirectional"))
    )
    (net (code "128") (name "unconnected-(U1-CH10-Pad17)") (class "Default")
      (node (ref "U1") (pin "17") (pinfunction "CH10_17") (pintype "bidirectional"))
    )
    (net (code "129") (name "unconnected-(U1-CH11-Pad18)") (class "Default")
      (node (ref "U1") (pin "18") (pinfunction "CH11_18") (pintype "bidirectional"))
    )
    (net (code "130") (name "unconnected-(U1-CH12-Pad19)") (class "Default")
      (node (ref "U1") (pin "19") (pinfunction "CH12_19") (pintype "bidirectional"))
    )
    (net (code "131") (name "unconnected-(U1-CH13-Pad20)") (class "Default")
      (node (ref "U1") (pin "20") (pinfunction "CH13_20") (pintype "bidirectional"))
    )
    (net (code "132") (name "unconnected-(U1-CH14-Pad21)") (class "Default")
      (node (ref "U1") (pin "21") (pinfunction "CH14_21") (pintype "bidirectional"))
    )
    (net (code "133") (name "unconnected-(U1-CH15-Pad22)") (class "Default")
      (node (ref "U1") (pin "22") (pinfunction "CH15_22") (pintype "bidirectional"))
    )
    (net (code "134") (name "unconnected-(V-THRUST_CURR_ADC-ALERT-PadP$2)") (class "Default")
      (node (ref "V-THRUST_CURR_ADC") (pin "P$2") (pinfunction "ALERT_P$2") (pintype "bidirectional"))
    )
  )
)
